# Sheet2.net
KiCad netlist of a schematic drawn in Altium Designer
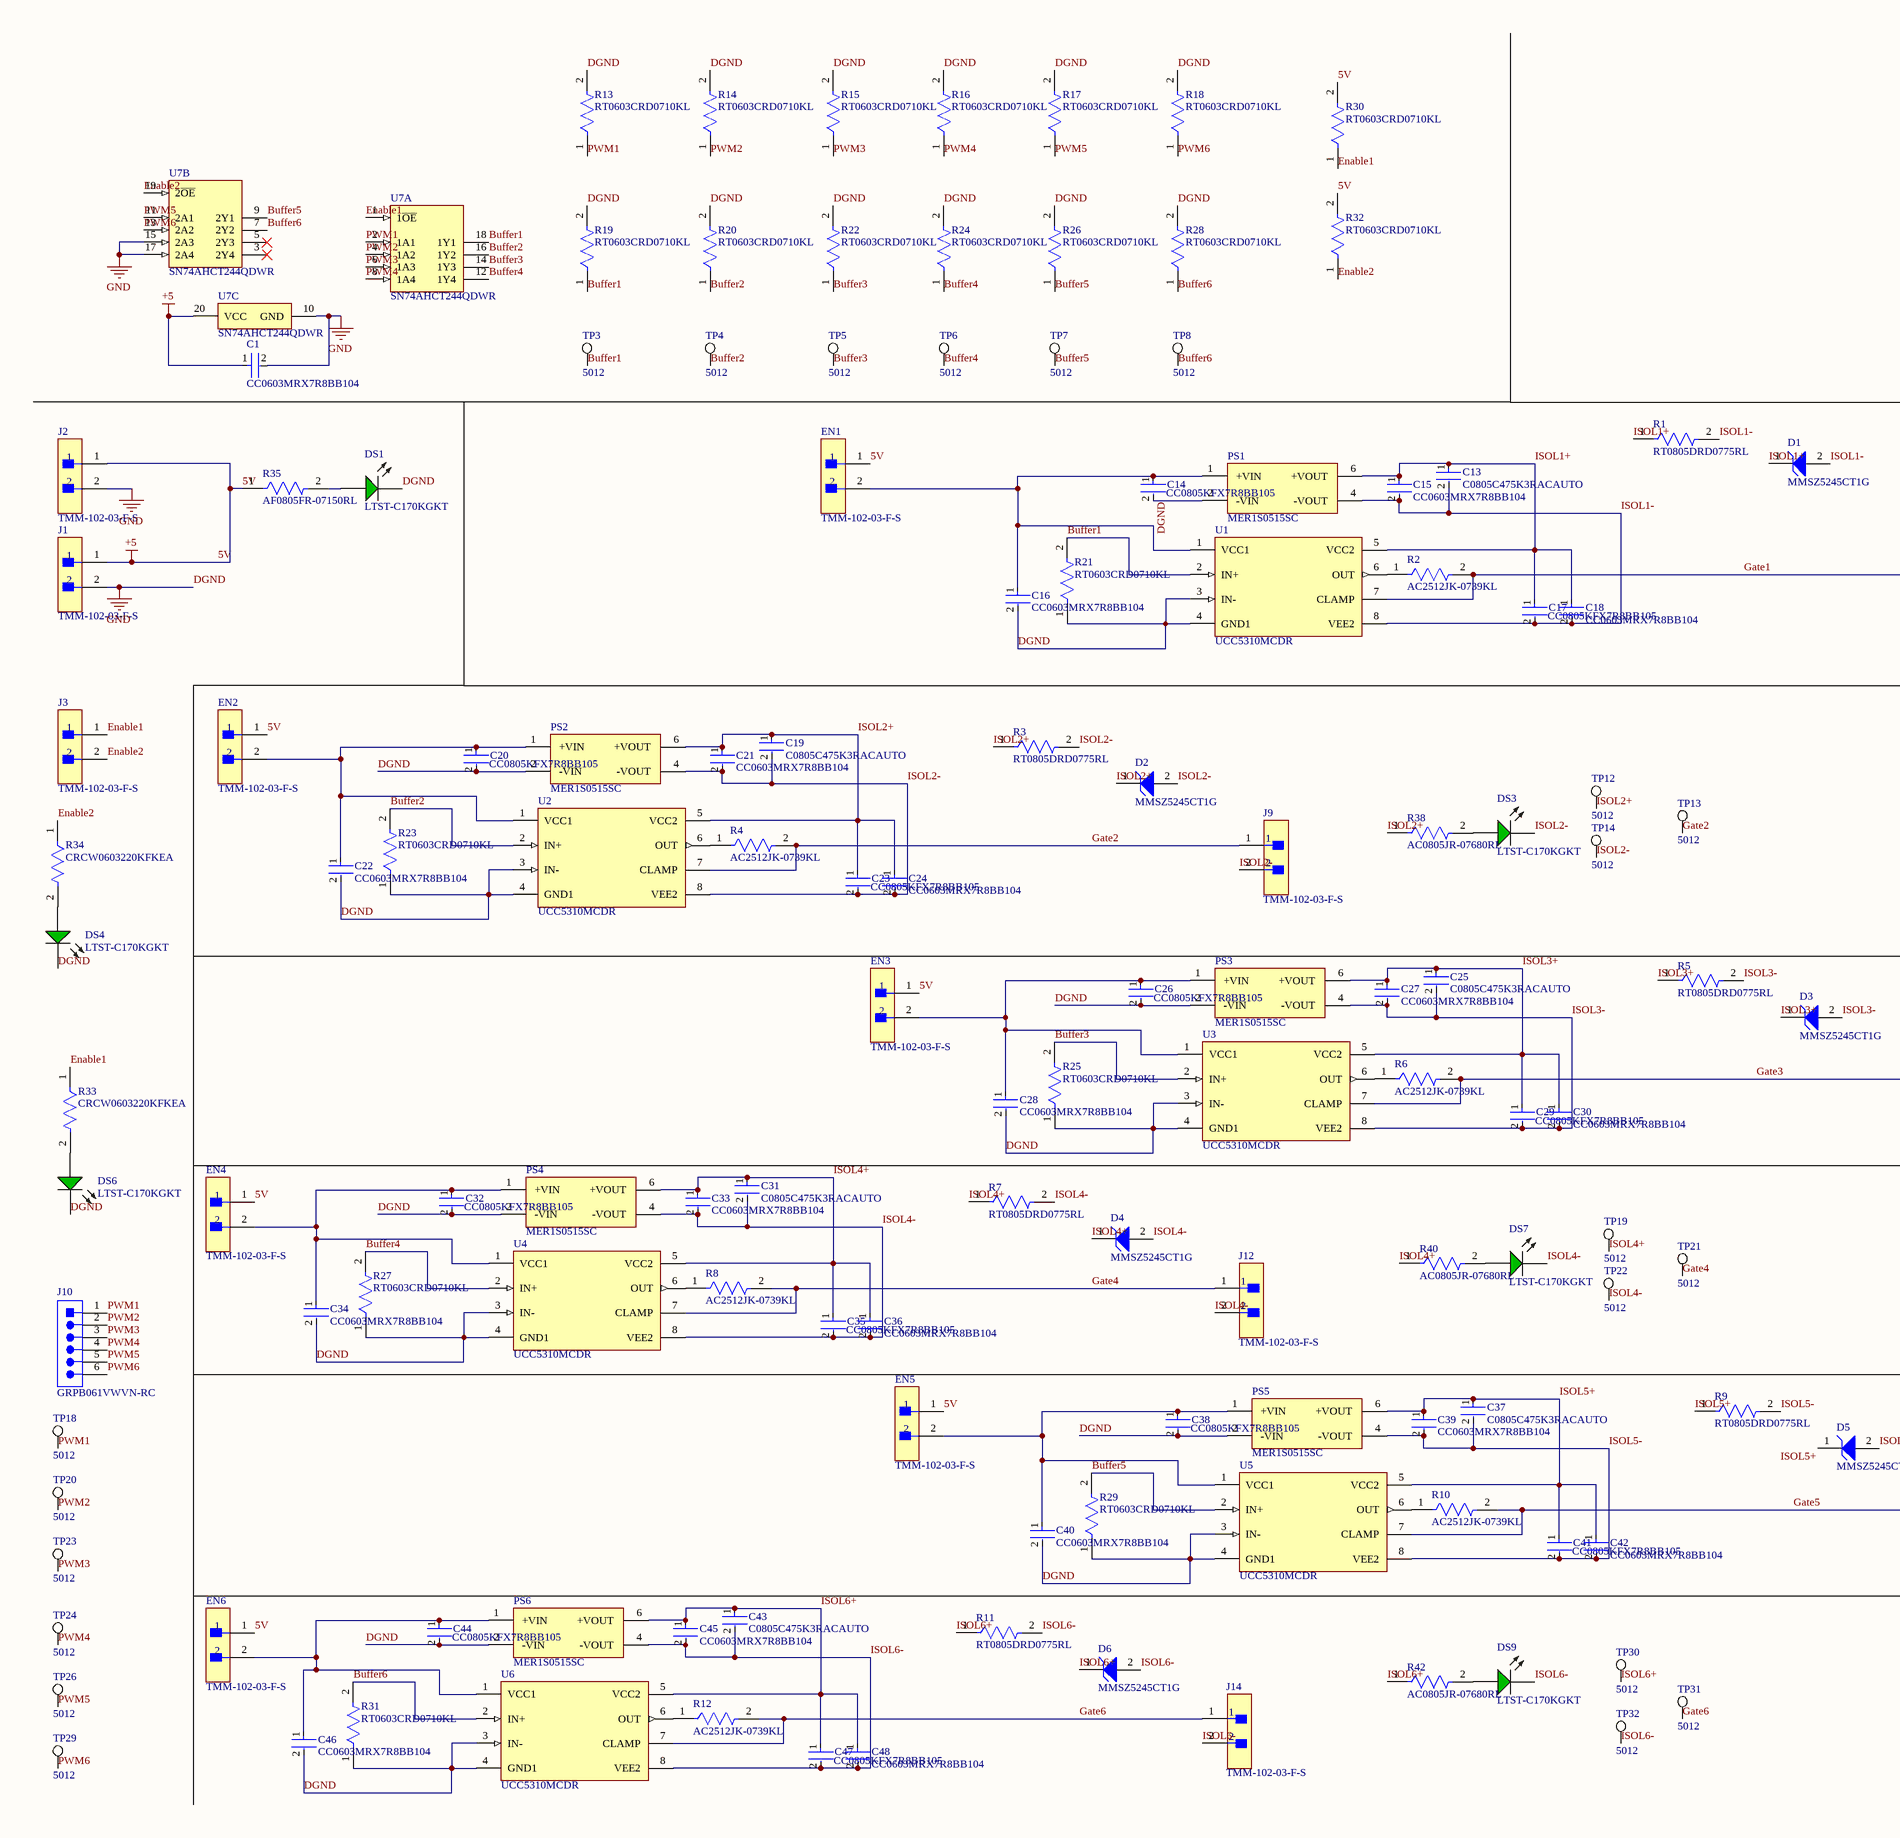
[diagram p0: Sheet2.SchDoc, left]
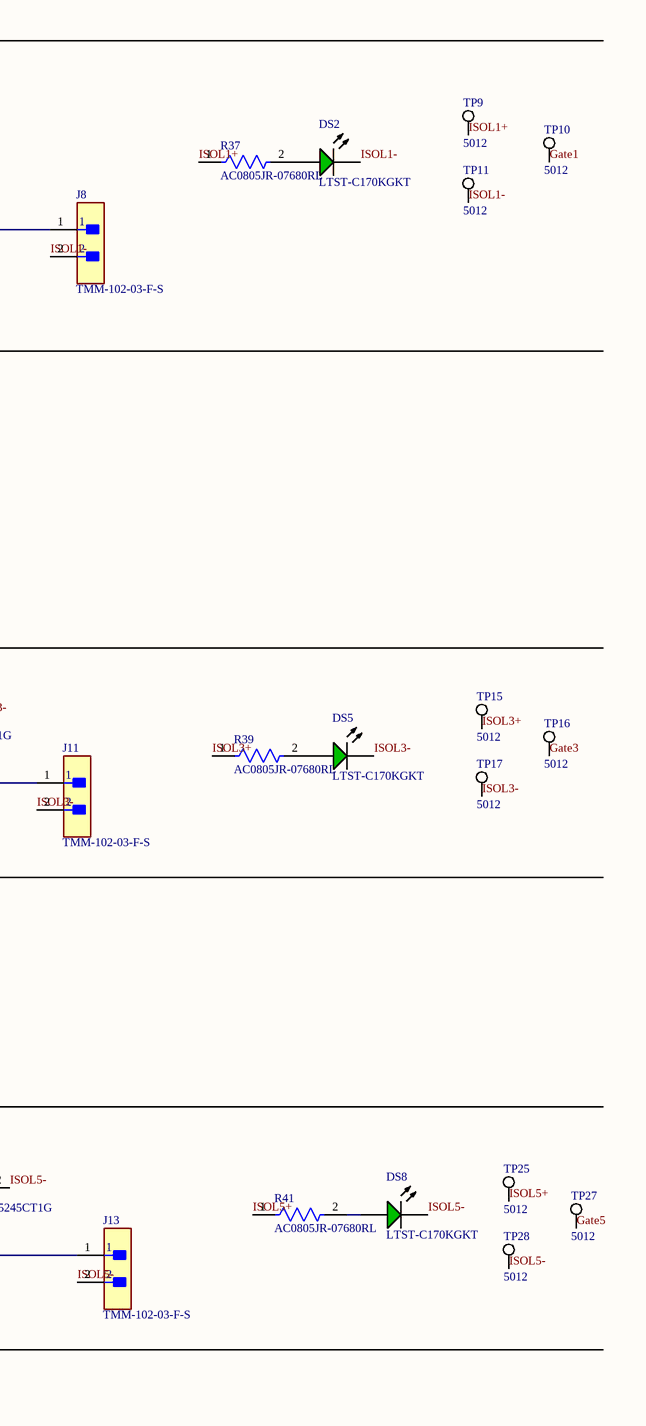
[diagram p1: Sheet2.SchDoc, right]

(export (version "E")
  (design (tool "Eeschema 10.0.6"))
  (components
    (comp (ref "C1")
      (value "CC0603MRX7R8BB104")
      (footprint "FP-CC0603-DA-MFG")
      (description "CAP CER 0.1UF 25V X7R 0603")
      (fields
        (field (name "TOLERANCE") "0.2")
        (field (name "OCTOPART") "https://octopart.com/cc0603mrx7r8bb104-yageo-12817663")
      )
      (libsource (lib "Altium Content Vault") (part "11868f565c42a9108669ba33697ecf6"))
    )
    (comp (ref "C13")
      (value "C0805C475K3RACAUTO")
      (footprint "FP-C0805C475K3RACAUTO-MFG")
      (description "CAP CER 0805 4.7UF 25V X7R  10%")
      (libsource (lib "Altium Content Vault") (part "b4654b650e69147ec39a6b967a45e02"))
    )
    (comp (ref "C14")
      (value "CC0805KFX7R8BB105")
      (footprint "FP-CC0805-0_85-MFG")
      (description "CC0805 1 uF X7R 10.00% 25 V")
      (fields (field (name "MANUFACTURER") "Yageo") (field (name "TOLERANCE") "0.1"))
      (libsource (lib "Altium Content Vault") (part "11868f565c42a9108669ba33697ecf6"))
    )
    (comp (ref "C15")
      (value "CC0603MRX7R8BB104")
      (footprint "FP-CC0603-DA-MFG")
      (description "CAP CER 0.1UF 25V X7R 0603")
      (fields
        (field (name "TOLERANCE") "0.2")
        (field (name "OCTOPART") "https://octopart.com/cc0603mrx7r8bb104-yageo-12817663")
      )
      (libsource (lib "Altium Content Vault") (part "11868f565c42a9108669ba33697ecf6"))
    )
    (comp (ref "C16")
      (value "CC0603MRX7R8BB104")
      (footprint "FP-CC0603-DA-MFG")
      (description "CAP CER 0.1UF 25V X7R 0603")
      (fields
        (field (name "TOLERANCE") "0.2")
        (field (name "OCTOPART") "https://octopart.com/cc0603mrx7r8bb104-yageo-12817663")
      )
      (libsource (lib "Altium Content Vault") (part "11868f565c42a9108669ba33697ecf6"))
    )
    (comp (ref "C17")
      (value "CC0805KFX7R8BB105")
      (footprint "FP-CC0805-0_85-MFG")
      (description "CC0805 1 uF X7R 10.00% 25 V")
      (fields (field (name "MANUFACTURER") "Yageo") (field (name "TOLERANCE") "0.1"))
      (libsource (lib "Altium Content Vault") (part "11868f565c42a9108669ba33697ecf6"))
    )
    (comp (ref "C18")
      (value "CC0603MRX7R8BB104")
      (footprint "FP-CC0603-DA-MFG")
      (description "CAP CER 0.1UF 25V X7R 0603")
      (fields
        (field (name "TOLERANCE") "0.2")
        (field (name "OCTOPART") "https://octopart.com/cc0603mrx7r8bb104-yageo-12817663")
      )
      (libsource (lib "Altium Content Vault") (part "11868f565c42a9108669ba33697ecf6"))
    )
    (comp (ref "C19")
      (value "C0805C475K3RACAUTO")
      (footprint "FP-C0805C475K3RACAUTO-MFG")
      (description "CAP CER 0805 4.7UF 25V X7R  10%")
      (libsource (lib "Altium Content Vault") (part "b4654b650e69147ec39a6b967a45e02"))
    )
    (comp (ref "C20")
      (value "CC0805KFX7R8BB105")
      (footprint "FP-CC0805-0_85-MFG")
      (description "CC0805 1 uF X7R 10.00% 25 V")
      (fields (field (name "MANUFACTURER") "Yageo") (field (name "TOLERANCE") "0.1"))
      (libsource (lib "Altium Content Vault") (part "11868f565c42a9108669ba33697ecf6"))
    )
    (comp (ref "C21")
      (value "CC0603MRX7R8BB104")
      (footprint "FP-CC0603-DA-MFG")
      (description "CAP CER 0.1UF 25V X7R 0603")
      (fields
        (field (name "TOLERANCE") "0.2")
        (field (name "OCTOPART") "https://octopart.com/cc0603mrx7r8bb104-yageo-12817663")
      )
      (libsource (lib "Altium Content Vault") (part "11868f565c42a9108669ba33697ecf6"))
    )
    (comp (ref "C22")
      (value "CC0603MRX7R8BB104")
      (footprint "FP-CC0603-DA-MFG")
      (description "CAP CER 0.1UF 25V X7R 0603")
      (fields
        (field (name "TOLERANCE") "0.2")
        (field (name "OCTOPART") "https://octopart.com/cc0603mrx7r8bb104-yageo-12817663")
      )
      (libsource (lib "Altium Content Vault") (part "11868f565c42a9108669ba33697ecf6"))
    )
    (comp (ref "C23")
      (value "CC0805KFX7R8BB105")
      (footprint "FP-CC0805-0_85-MFG")
      (description "CC0805 1 uF X7R 10.00% 25 V")
      (fields (field (name "MANUFACTURER") "Yageo") (field (name "TOLERANCE") "0.1"))
      (libsource (lib "Altium Content Vault") (part "11868f565c42a9108669ba33697ecf6"))
    )
    (comp (ref "C24")
      (value "CC0603MRX7R8BB104")
      (footprint "FP-CC0603-DA-MFG")
      (description "CAP CER 0.1UF 25V X7R 0603")
      (fields
        (field (name "TOLERANCE") "0.2")
        (field (name "OCTOPART") "https://octopart.com/cc0603mrx7r8bb104-yageo-12817663")
      )
      (libsource (lib "Altium Content Vault") (part "11868f565c42a9108669ba33697ecf6"))
    )
    (comp (ref "C25")
      (value "C0805C475K3RACAUTO")
      (footprint "FP-C0805C475K3RACAUTO-MFG")
      (description "CAP CER 0805 4.7UF 25V X7R  10%")
      (libsource (lib "Altium Content Vault") (part "b4654b650e69147ec39a6b967a45e02"))
    )
    (comp (ref "C26")
      (value "CC0805KFX7R8BB105")
      (footprint "FP-CC0805-0_85-MFG")
      (description "CC0805 1 uF X7R 10.00% 25 V")
      (fields (field (name "MANUFACTURER") "Yageo") (field (name "TOLERANCE") "0.1"))
      (libsource (lib "Altium Content Vault") (part "11868f565c42a9108669ba33697ecf6"))
    )
    (comp (ref "C27")
      (value "CC0603MRX7R8BB104")
      (footprint "FP-CC0603-DA-MFG")
      (description "CAP CER 0.1UF 25V X7R 0603")
      (fields
        (field (name "TOLERANCE") "0.2")
        (field (name "OCTOPART") "https://octopart.com/cc0603mrx7r8bb104-yageo-12817663")
      )
      (libsource (lib "Altium Content Vault") (part "11868f565c42a9108669ba33697ecf6"))
    )
    (comp (ref "C28")
      (value "CC0603MRX7R8BB104")
      (footprint "FP-CC0603-DA-MFG")
      (description "CAP CER 0.1UF 25V X7R 0603")
      (fields
        (field (name "TOLERANCE") "0.2")
        (field (name "OCTOPART") "https://octopart.com/cc0603mrx7r8bb104-yageo-12817663")
      )
      (libsource (lib "Altium Content Vault") (part "11868f565c42a9108669ba33697ecf6"))
    )
    (comp (ref "C29")
      (value "CC0805KFX7R8BB105")
      (footprint "FP-CC0805-0_85-MFG")
      (description "CC0805 1 uF X7R 10.00% 25 V")
      (fields (field (name "MANUFACTURER") "Yageo") (field (name "TOLERANCE") "0.1"))
      (libsource (lib "Altium Content Vault") (part "11868f565c42a9108669ba33697ecf6"))
    )
    (comp (ref "C30")
      (value "CC0603MRX7R8BB104")
      (footprint "FP-CC0603-DA-MFG")
      (description "CAP CER 0.1UF 25V X7R 0603")
      (fields
        (field (name "TOLERANCE") "0.2")
        (field (name "OCTOPART") "https://octopart.com/cc0603mrx7r8bb104-yageo-12817663")
      )
      (libsource (lib "Altium Content Vault") (part "11868f565c42a9108669ba33697ecf6"))
    )
    (comp (ref "C31")
      (value "C0805C475K3RACAUTO")
      (footprint "FP-C0805C475K3RACAUTO-MFG")
      (description "CAP CER 0805 4.7UF 25V X7R  10%")
      (libsource (lib "Altium Content Vault") (part "b4654b650e69147ec39a6b967a45e02"))
    )
    (comp (ref "C32")
      (value "CC0805KFX7R8BB105")
      (footprint "FP-CC0805-0_85-MFG")
      (description "CC0805 1 uF X7R 10.00% 25 V")
      (fields (field (name "MANUFACTURER") "Yageo") (field (name "TOLERANCE") "0.1"))
      (libsource (lib "Altium Content Vault") (part "11868f565c42a9108669ba33697ecf6"))
    )
    (comp (ref "C33")
      (value "CC0603MRX7R8BB104")
      (footprint "FP-CC0603-DA-MFG")
      (description "CAP CER 0.1UF 25V X7R 0603")
      (fields
        (field (name "TOLERANCE") "0.2")
        (field (name "OCTOPART") "https://octopart.com/cc0603mrx7r8bb104-yageo-12817663")
      )
      (libsource (lib "Altium Content Vault") (part "11868f565c42a9108669ba33697ecf6"))
    )
    (comp (ref "C34")
      (value "CC0603MRX7R8BB104")
      (footprint "FP-CC0603-DA-MFG")
      (description "CAP CER 0.1UF 25V X7R 0603")
      (fields
        (field (name "TOLERANCE") "0.2")
        (field (name "OCTOPART") "https://octopart.com/cc0603mrx7r8bb104-yageo-12817663")
      )
      (libsource (lib "Altium Content Vault") (part "11868f565c42a9108669ba33697ecf6"))
    )
    (comp (ref "C35")
      (value "CC0805KFX7R8BB105")
      (footprint "FP-CC0805-0_85-MFG")
      (description "CC0805 1 uF X7R 10.00% 25 V")
      (fields (field (name "MANUFACTURER") "Yageo") (field (name "TOLERANCE") "0.1"))
      (libsource (lib "Altium Content Vault") (part "11868f565c42a9108669ba33697ecf6"))
    )
    (comp (ref "C36")
      (value "CC0603MRX7R8BB104")
      (footprint "FP-CC0603-DA-MFG")
      (description "CAP CER 0.1UF 25V X7R 0603")
      (fields
        (field (name "TOLERANCE") "0.2")
        (field (name "OCTOPART") "https://octopart.com/cc0603mrx7r8bb104-yageo-12817663")
      )
      (libsource (lib "Altium Content Vault") (part "11868f565c42a9108669ba33697ecf6"))
    )
    (comp (ref "C37")
      (value "C0805C475K3RACAUTO")
      (footprint "FP-C0805C475K3RACAUTO-MFG")
      (description "CAP CER 0805 4.7UF 25V X7R  10%")
      (libsource (lib "Altium Content Vault") (part "b4654b650e69147ec39a6b967a45e02"))
    )
    (comp (ref "C38")
      (value "CC0805KFX7R8BB105")
      (footprint "FP-CC0805-0_85-MFG")
      (description "CC0805 1 uF X7R 10.00% 25 V")
      (fields (field (name "MANUFACTURER") "Yageo") (field (name "TOLERANCE") "0.1"))
      (libsource (lib "Altium Content Vault") (part "11868f565c42a9108669ba33697ecf6"))
    )
    (comp (ref "C39")
      (value "CC0603MRX7R8BB104")
      (footprint "FP-CC0603-DA-MFG")
      (description "CAP CER 0.1UF 25V X7R 0603")
      (fields
        (field (name "TOLERANCE") "0.2")
        (field (name "OCTOPART") "https://octopart.com/cc0603mrx7r8bb104-yageo-12817663")
      )
      (libsource (lib "Altium Content Vault") (part "11868f565c42a9108669ba33697ecf6"))
    )
    (comp (ref "C40")
      (value "CC0603MRX7R8BB104")
      (footprint "FP-CC0603-DA-MFG")
      (description "CAP CER 0.1UF 25V X7R 0603")
      (fields
        (field (name "TOLERANCE") "0.2")
        (field (name "OCTOPART") "https://octopart.com/cc0603mrx7r8bb104-yageo-12817663")
      )
      (libsource (lib "Altium Content Vault") (part "11868f565c42a9108669ba33697ecf6"))
    )
    (comp (ref "C41")
      (value "CC0805KFX7R8BB105")
      (footprint "FP-CC0805-0_85-MFG")
      (description "CC0805 1 uF X7R 10.00% 25 V")
      (fields (field (name "MANUFACTURER") "Yageo") (field (name "TOLERANCE") "0.1"))
      (libsource (lib "Altium Content Vault") (part "11868f565c42a9108669ba33697ecf6"))
    )
    (comp (ref "C42")
      (value "CC0603MRX7R8BB104")
      (footprint "FP-CC0603-DA-MFG")
      (description "CAP CER 0.1UF 25V X7R 0603")
      (fields
        (field (name "TOLERANCE") "0.2")
        (field (name "OCTOPART") "https://octopart.com/cc0603mrx7r8bb104-yageo-12817663")
      )
      (libsource (lib "Altium Content Vault") (part "11868f565c42a9108669ba33697ecf6"))
    )
    (comp (ref "C43")
      (value "C0805C475K3RACAUTO")
      (footprint "FP-C0805C475K3RACAUTO-MFG")
      (description "CAP CER 0805 4.7UF 25V X7R  10%")
      (libsource (lib "Altium Content Vault") (part "b4654b650e69147ec39a6b967a45e02"))
    )
    (comp (ref "C44")
      (value "CC0805KFX7R8BB105")
      (footprint "FP-CC0805-0_85-MFG")
      (description "CC0805 1 uF X7R 10.00% 25 V")
      (fields (field (name "MANUFACTURER") "Yageo") (field (name "TOLERANCE") "0.1"))
      (libsource (lib "Altium Content Vault") (part "11868f565c42a9108669ba33697ecf6"))
    )
    (comp (ref "C45")
      (value "CC0603MRX7R8BB104")
      (footprint "FP-CC0603-DA-MFG")
      (description "CAP CER 0.1UF 25V X7R 0603")
      (fields
        (field (name "TOLERANCE") "0.2")
        (field (name "OCTOPART") "https://octopart.com/cc0603mrx7r8bb104-yageo-12817663")
      )
      (libsource (lib "Altium Content Vault") (part "11868f565c42a9108669ba33697ecf6"))
    )
    (comp (ref "C46")
      (value "CC0603MRX7R8BB104")
      (footprint "FP-CC0603-DA-MFG")
      (description "CAP CER 0.1UF 25V X7R 0603")
      (fields
        (field (name "TOLERANCE") "0.2")
        (field (name "OCTOPART") "https://octopart.com/cc0603mrx7r8bb104-yageo-12817663")
      )
      (libsource (lib "Altium Content Vault") (part "11868f565c42a9108669ba33697ecf6"))
    )
    (comp (ref "C47")
      (value "CC0805KFX7R8BB105")
      (footprint "FP-CC0805-0_85-MFG")
      (description "CC0805 1 uF X7R 10.00% 25 V")
      (fields (field (name "MANUFACTURER") "Yageo") (field (name "TOLERANCE") "0.1"))
      (libsource (lib "Altium Content Vault") (part "11868f565c42a9108669ba33697ecf6"))
    )
    (comp (ref "C48")
      (value "CC0603MRX7R8BB104")
      (footprint "FP-CC0603-DA-MFG")
      (description "CAP CER 0.1UF 25V X7R 0603")
      (fields
        (field (name "TOLERANCE") "0.2")
        (field (name "OCTOPART") "https://octopart.com/cc0603mrx7r8bb104-yageo-12817663")
      )
      (libsource (lib "Altium Content Vault") (part "11868f565c42a9108669ba33697ecf6"))
    )
    (comp (ref "D1")
      (value "MMSZ5245CT1G")
      (footprint "ONSC-SOD-123-2-425-04_V")
      (description "Zener Voltage Regulator, 500 mW, 2-Pin SOD-123, Pb-Free, Tape and Reel")
      (fields (field (name "MANUFACTURER") "On Semiconductor"))
      (libsource (lib "Altium Content Vault") (part "ONSC-K1A2-2"))
    )
    (comp (ref "D2")
      (value "MMSZ5245CT1G")
      (footprint "ONSC-SOD-123-2-425-04_V")
      (description "Zener Voltage Regulator, 500 mW, 2-Pin SOD-123, Pb-Free, Tape and Reel")
      (fields (field (name "MANUFACTURER") "On Semiconductor"))
      (libsource (lib "Altium Content Vault") (part "ONSC-K1A2-2"))
    )
    (comp (ref "D3")
      (value "MMSZ5245CT1G")
      (footprint "ONSC-SOD-123-2-425-04_V")
      (description "Zener Voltage Regulator, 500 mW, 2-Pin SOD-123, Pb-Free, Tape and Reel")
      (fields (field (name "MANUFACTURER") "On Semiconductor"))
      (libsource (lib "Altium Content Vault") (part "ONSC-K1A2-2"))
    )
    (comp (ref "D4")
      (value "MMSZ5245CT1G")
      (footprint "ONSC-SOD-123-2-425-04_V")
      (description "Zener Voltage Regulator, 500 mW, 2-Pin SOD-123, Pb-Free, Tape and Reel")
      (fields (field (name "MANUFACTURER") "On Semiconductor"))
      (libsource (lib "Altium Content Vault") (part "ONSC-K1A2-2"))
    )
    (comp (ref "D5")
      (value "MMSZ5245CT1G")
      (footprint "ONSC-SOD-123-2-425-04_V")
      (description "Zener Voltage Regulator, 500 mW, 2-Pin SOD-123, Pb-Free, Tape and Reel")
      (fields (field (name "MANUFACTURER") "On Semiconductor"))
      (libsource (lib "Altium Content Vault") (part "ONSC-K1A2-2"))
    )
    (comp (ref "D6")
      (value "MMSZ5245CT1G")
      (footprint "ONSC-SOD-123-2-425-04_V")
      (description "Zener Voltage Regulator, 500 mW, 2-Pin SOD-123, Pb-Free, Tape and Reel")
      (fields (field (name "MANUFACTURER") "On Semiconductor"))
      (libsource (lib "Altium Content Vault") (part "ONSC-K1A2-2"))
    )
    (comp (ref "DS1")
      (value "LTST-C170KGKT")
      (footprint "LTST-LTST-C170KGKT-2_V")
      (description "Ultra Bright AlInGaP Chip LED, 75 mW, -55 to 85 degC, 2-Pin SMD (0805), RoHS, Tape and Reel")
      (fields (field (name "MANUFACTURER") "Lite-On"))
      (libsource (lib "Altium Content Vault") (part "LED-GREEN-KA-2"))
    )
    (comp (ref "DS2")
      (value "LTST-C170KGKT")
      (footprint "LTST-LTST-C170KGKT-2_V")
      (description "Ultra Bright AlInGaP Chip LED, 75 mW, -55 to 85 degC, 2-Pin SMD (0805), RoHS, Tape and Reel")
      (fields (field (name "MANUFACTURER") "Lite-On"))
      (libsource (lib "Altium Content Vault") (part "LED-GREEN-KA-2"))
    )
    (comp (ref "DS3")
      (value "LTST-C170KGKT")
      (footprint "LTST-LTST-C170KGKT-2_V")
      (description "Ultra Bright AlInGaP Chip LED, 75 mW, -55 to 85 degC, 2-Pin SMD (0805), RoHS, Tape and Reel")
      (fields (field (name "MANUFACTURER") "Lite-On"))
      (libsource (lib "Altium Content Vault") (part "LED-GREEN-KA-2"))
    )
    (comp (ref "DS4")
      (value "LTST-C170KGKT")
      (footprint "LTST-LTST-C170KGKT-2_V")
      (description "Ultra Bright AlInGaP Chip LED, 75 mW, -55 to 85 degC, 2-Pin SMD (0805), RoHS, Tape and Reel")
      (fields (field (name "MANUFACTURER") "Lite-On"))
      (libsource (lib "Altium Content Vault") (part "LED-GREEN-KA-2"))
    )
    (comp (ref "DS5")
      (value "LTST-C170KGKT")
      (footprint "LTST-LTST-C170KGKT-2_V")
      (description "Ultra Bright AlInGaP Chip LED, 75 mW, -55 to 85 degC, 2-Pin SMD (0805), RoHS, Tape and Reel")
      (fields (field (name "MANUFACTURER") "Lite-On"))
      (libsource (lib "Altium Content Vault") (part "LED-GREEN-KA-2"))
    )
    (comp (ref "DS6")
      (value "LTST-C170KGKT")
      (footprint "LTST-LTST-C170KGKT-2_V")
      (description "Ultra Bright AlInGaP Chip LED, 75 mW, -55 to 85 degC, 2-Pin SMD (0805), RoHS, Tape and Reel")
      (fields (field (name "MANUFACTURER") "Lite-On"))
      (libsource (lib "Altium Content Vault") (part "LED-GREEN-KA-2"))
    )
    (comp (ref "DS7")
      (value "LTST-C170KGKT")
      (footprint "LTST-LTST-C170KGKT-2_V")
      (description "Ultra Bright AlInGaP Chip LED, 75 mW, -55 to 85 degC, 2-Pin SMD (0805), RoHS, Tape and Reel")
      (fields (field (name "MANUFACTURER") "Lite-On"))
      (libsource (lib "Altium Content Vault") (part "LED-GREEN-KA-2"))
    )
    (comp (ref "DS8")
      (value "LTST-C170KGKT")
      (footprint "LTST-LTST-C170KGKT-2_V")
      (description "Ultra Bright AlInGaP Chip LED, 75 mW, -55 to 85 degC, 2-Pin SMD (0805), RoHS, Tape and Reel")
      (fields (field (name "MANUFACTURER") "Lite-On"))
      (libsource (lib "Altium Content Vault") (part "LED-GREEN-KA-2"))
    )
    (comp (ref "DS9")
      (value "LTST-C170KGKT")
      (footprint "LTST-LTST-C170KGKT-2_V")
      (description "Ultra Bright AlInGaP Chip LED, 75 mW, -55 to 85 degC, 2-Pin SMD (0805), RoHS, Tape and Reel")
      (fields (field (name "MANUFACTURER") "Lite-On"))
      (libsource (lib "Altium Content Vault") (part "LED-GREEN-KA-2"))
    )
    (comp (ref "EN1")
      (value "TMM-102-03-F-S")
      (footprint "GPIO_Headers:PinHeader_1x02_P2.54mm_Vertical")
      (description "CONN HEADER VERT 2POS 2MM")
      (libsource (lib "Altium Content Vault") (part "3bc925449376181038e59eaffc5286c"))
    )
    (comp (ref "EN2")
      (value "TMM-102-03-F-S")
      (footprint "GPIO_Headers:PinHeader_1x02_P2.54mm_Vertical")
      (description "CONN HEADER VERT 2POS 2MM")
      (libsource (lib "Altium Content Vault") (part "3bc925449376181038e59eaffc5286c"))
    )
    (comp (ref "EN3")
      (value "TMM-102-03-F-S")
      (footprint "GPIO_Headers:PinHeader_1x02_P2.54mm_Vertical")
      (description "CONN HEADER VERT 2POS 2MM")
      (libsource (lib "Altium Content Vault") (part "3bc925449376181038e59eaffc5286c"))
    )
    (comp (ref "EN4")
      (value "TMM-102-03-F-S")
      (footprint "GPIO_Headers:PinHeader_1x02_P2.54mm_Vertical")
      (description "CONN HEADER VERT 2POS 2MM")
      (libsource (lib "Altium Content Vault") (part "3bc925449376181038e59eaffc5286c"))
    )
    (comp (ref "EN5")
      (value "TMM-102-03-F-S")
      (footprint "GPIO_Headers:PinHeader_1x02_P2.54mm_Vertical")
      (description "CONN HEADER VERT 2POS 2MM")
      (libsource (lib "Altium Content Vault") (part "3bc925449376181038e59eaffc5286c"))
    )
    (comp (ref "EN6")
      (value "TMM-102-03-F-S")
      (footprint "GPIO_Headers:PinHeader_1x02_P2.54mm_Vertical")
      (description "CONN HEADER VERT 2POS 2MM")
      (libsource (lib "Altium Content Vault") (part "3bc925449376181038e59eaffc5286c"))
    )
    (comp (ref "J1")
      (value "TMM-102-03-F-S")
      (footprint "GPIO_Headers:PinHeader_1x02_P2.54mm_Vertical")
      (description "CONN HEADER VERT 2POS 2MM")
      (libsource (lib "Altium Content Vault") (part "3bc925449376181038e59eaffc5286c"))
    )
    (comp (ref "J2")
      (value "TMM-102-03-F-S")
      (footprint "GPIO_Headers:PinHeader_1x02_P2.54mm_Vertical")
      (description "CONN HEADER VERT 2POS 2MM")
      (libsource (lib "Altium Content Vault") (part "3bc925449376181038e59eaffc5286c"))
    )
    (comp (ref "J3")
      (value "TMM-102-03-F-S")
      (footprint "GPIO_Headers:PinHeader_1x02_P2.54mm_Vertical")
      (description "CONN HEADER VERT 2POS 2MM")
      (libsource (lib "Altium Content Vault") (part "3bc925449376181038e59eaffc5286c"))
    )
    (comp (ref "J8")
      (value "TMM-102-03-F-S")
      (footprint "GPIO_Headers:PinHeader_1x02_P2.54mm_Vertical")
      (description "CONN HEADER VERT 2POS 2MM")
      (libsource (lib "") (part "3bc925449376181038e59eaffc5286c_1"))
    )
    (comp (ref "J9")
      (value "TMM-102-03-F-S")
      (footprint "GPIO_Headers:PinHeader_1x02_P2.54mm_Vertical")
      (description "CONN HEADER VERT 2POS 2MM")
      (libsource (lib "") (part "3bc925449376181038e59eaffc5286c_1"))
    )
    (comp (ref "J10")
      (value "GRPB061VWVN-RC")
      (footprint "GPIO_Headers:PinHeader_1x06_P2.54mm_Vertical")
      (fields (field (name "MANUFACTURER") "Sullins"))
      (libsource (lib "Altium Content Vault") (part "CN-1P-M-R6"))
    )
    (comp (ref "J11")
      (value "TMM-102-03-F-S")
      (footprint "GPIO_Headers:PinHeader_1x02_P2.54mm_Vertical")
      (description "CONN HEADER VERT 2POS 2MM")
      (libsource (lib "") (part "3bc925449376181038e59eaffc5286c_1"))
    )
    (comp (ref "J12")
      (value "TMM-102-03-F-S")
      (footprint "GPIO_Headers:PinHeader_1x02_P2.54mm_Vertical")
      (description "CONN HEADER VERT 2POS 2MM")
      (libsource (lib "") (part "3bc925449376181038e59eaffc5286c_1"))
    )
    (comp (ref "J13")
      (value "TMM-102-03-F-S")
      (footprint "GPIO_Headers:PinHeader_1x02_P2.54mm_Vertical")
      (description "CONN HEADER VERT 2POS 2MM")
      (libsource (lib "") (part "3bc925449376181038e59eaffc5286c_1"))
    )
    (comp (ref "J14")
      (value "TMM-102-03-F-S")
      (footprint "GPIO_Headers:PinHeader_1x02_P2.54mm_Vertical")
      (description "CONN HEADER VERT 2POS 2MM")
      (libsource (lib "") (part "3bc925449376181038e59eaffc5286c_1"))
    )
    (comp (ref "PS1")
      (value "MER1S0515SC")
      (footprint "MER1S0515SC_MFG")
      (description "Module DC-DC 5VIN 1-OUT 15V 0.067A 1W 4-Pin SIP Tube")
      (libsource (lib "Altium Content Vault") (part "aca5a9e5ed4e940d1217dfa819842fb"))
    )
    (comp (ref "PS2")
      (value "MER1S0515SC")
      (footprint "MER1S0515SC_MFG")
      (description "Module DC-DC 5VIN 1-OUT 15V 0.067A 1W 4-Pin SIP Tube")
      (libsource (lib "Altium Content Vault") (part "aca5a9e5ed4e940d1217dfa819842fb"))
    )
    (comp (ref "PS3")
      (value "MER1S0515SC")
      (footprint "MER1S0515SC_MFG")
      (description "Module DC-DC 5VIN 1-OUT 15V 0.067A 1W 4-Pin SIP Tube")
      (libsource (lib "Altium Content Vault") (part "aca5a9e5ed4e940d1217dfa819842fb"))
    )
    (comp (ref "PS4")
      (value "MER1S0515SC")
      (footprint "MER1S0515SC_MFG")
      (description "Module DC-DC 5VIN 1-OUT 15V 0.067A 1W 4-Pin SIP Tube")
      (libsource (lib "Altium Content Vault") (part "aca5a9e5ed4e940d1217dfa819842fb"))
    )
    (comp (ref "PS5")
      (value "MER1S0515SC")
      (footprint "MER1S0515SC_MFG")
      (description "Module DC-DC 5VIN 1-OUT 15V 0.067A 1W 4-Pin SIP Tube")
      (libsource (lib "Altium Content Vault") (part "aca5a9e5ed4e940d1217dfa819842fb"))
    )
    (comp (ref "PS6")
      (value "MER1S0515SC")
      (footprint "MER1S0515SC_MFG")
      (description "Module DC-DC 5VIN 1-OUT 15V 0.067A 1W 4-Pin SIP Tube")
      (libsource (lib "Altium Content Vault") (part "aca5a9e5ed4e940d1217dfa819842fb"))
    )
    (comp (ref "R1")
      (value "RT0805DRD0775RL")
      (footprint "FP-RT0805-MFG")
      (description "RES SMD 75 OHM 0.5% 1/8W 0805")
      (fields (field (name "TOLERANCE") "0.01") (field (name "MANUFACTURER") "Yageo"))
      (libsource (lib "Altium Content Vault") (part "1029c3af85768c4190bb7ad29bc67b5"))
    )
    (comp (ref "R2")
      (value "AC2512JK-0739KL")
      (footprint "FP-AC2512-MFG")
      (description "RES SMD 39K OHM 5% 1W 2512")
      (fields
        (field (name "OCTOPART") "https://octopart.com/ac2512jk-0739kl-yageo-71370377")
        (field (name "TOLERANCE") "0.05")
      )
      (libsource (lib "Altium Content Vault") (part "1029c3af85768c4190bb7ad29bc67b5"))
    )
    (comp (ref "R3")
      (value "RT0805DRD0775RL")
      (footprint "FP-RT0805-MFG")
      (description "RES SMD 75 OHM 0.5% 1/8W 0805")
      (fields (field (name "TOLERANCE") "0.01") (field (name "MANUFACTURER") "Yageo"))
      (libsource (lib "Altium Content Vault") (part "1029c3af85768c4190bb7ad29bc67b5"))
    )
    (comp (ref "R4")
      (value "AC2512JK-0739KL")
      (footprint "FP-AC2512-MFG")
      (description "RES SMD 39K OHM 5% 1W 2512")
      (fields
        (field (name "OCTOPART") "https://octopart.com/ac2512jk-0739kl-yageo-71370377")
        (field (name "TOLERANCE") "0.05")
      )
      (libsource (lib "Altium Content Vault") (part "1029c3af85768c4190bb7ad29bc67b5"))
    )
    (comp (ref "R5")
      (value "RT0805DRD0775RL")
      (footprint "FP-RT0805-MFG")
      (description "RES SMD 75 OHM 0.5% 1/8W 0805")
      (fields (field (name "TOLERANCE") "0.01") (field (name "MANUFACTURER") "Yageo"))
      (libsource (lib "Altium Content Vault") (part "1029c3af85768c4190bb7ad29bc67b5"))
    )
    (comp (ref "R6")
      (value "AC2512JK-0739KL")
      (footprint "FP-AC2512-MFG")
      (description "RES SMD 39K OHM 5% 1W 2512")
      (fields
        (field (name "OCTOPART") "https://octopart.com/ac2512jk-0739kl-yageo-71370377")
        (field (name "TOLERANCE") "0.05")
      )
      (libsource (lib "Altium Content Vault") (part "1029c3af85768c4190bb7ad29bc67b5"))
    )
    (comp (ref "R7")
      (value "RT0805DRD0775RL")
      (footprint "FP-RT0805-MFG")
      (description "RES SMD 75 OHM 0.5% 1/8W 0805")
      (fields (field (name "TOLERANCE") "0.01") (field (name "MANUFACTURER") "Yageo"))
      (libsource (lib "Altium Content Vault") (part "1029c3af85768c4190bb7ad29bc67b5"))
    )
    (comp (ref "R8")
      (value "AC2512JK-0739KL")
      (footprint "FP-AC2512-MFG")
      (description "RES SMD 39K OHM 5% 1W 2512")
      (fields
        (field (name "OCTOPART") "https://octopart.com/ac2512jk-0739kl-yageo-71370377")
        (field (name "TOLERANCE") "0.05")
      )
      (libsource (lib "Altium Content Vault") (part "1029c3af85768c4190bb7ad29bc67b5"))
    )
    (comp (ref "R9")
      (value "RT0805DRD0775RL")
      (footprint "FP-RT0805-MFG")
      (description "RES SMD 75 OHM 0.5% 1/8W 0805")
      (fields (field (name "TOLERANCE") "0.01") (field (name "MANUFACTURER") "Yageo"))
      (libsource (lib "Altium Content Vault") (part "1029c3af85768c4190bb7ad29bc67b5"))
    )
    (comp (ref "R10")
      (value "AC2512JK-0739KL")
      (footprint "FP-AC2512-MFG")
      (description "RES SMD 39K OHM 5% 1W 2512")
      (fields
        (field (name "OCTOPART") "https://octopart.com/ac2512jk-0739kl-yageo-71370377")
        (field (name "TOLERANCE") "0.05")
      )
      (libsource (lib "Altium Content Vault") (part "1029c3af85768c4190bb7ad29bc67b5"))
    )
    (comp (ref "R11")
      (value "RT0805DRD0775RL")
      (footprint "FP-RT0805-MFG")
      (description "RES SMD 75 OHM 0.5% 1/8W 0805")
      (fields (field (name "TOLERANCE") "0.01") (field (name "MANUFACTURER") "Yageo"))
      (libsource (lib "Altium Content Vault") (part "1029c3af85768c4190bb7ad29bc67b5"))
    )
    (comp (ref "R12")
      (value "AC2512JK-0739KL")
      (footprint "FP-AC2512-MFG")
      (description "RES SMD 39K OHM 5% 1W 2512")
      (fields
        (field (name "OCTOPART") "https://octopart.com/ac2512jk-0739kl-yageo-71370377")
        (field (name "TOLERANCE") "0.05")
      )
      (libsource (lib "Altium Content Vault") (part "1029c3af85768c4190bb7ad29bc67b5"))
    )
    (comp (ref "R13")
      (value "RT0603CRD0710KL")
      (footprint "FP-RT0603-MFG")
      (description "RES SMD 10K OHM 0.25% 1/10W 0603")
      (fields (field (name "TOLERANCE") "0.0025") (field (name "MANUFACTURER") "Yageo"))
      (libsource (lib "Altium Content Vault") (part "1029c3af85768c4190bb7ad29bc67b5"))
    )
    (comp (ref "R14")
      (value "RT0603CRD0710KL")
      (footprint "FP-RT0603-MFG")
      (description "RES SMD 10K OHM 0.25% 1/10W 0603")
      (fields (field (name "TOLERANCE") "0.0025") (field (name "MANUFACTURER") "Yageo"))
      (libsource (lib "Altium Content Vault") (part "1029c3af85768c4190bb7ad29bc67b5"))
    )
    (comp (ref "R15")
      (value "RT0603CRD0710KL")
      (footprint "FP-RT0603-MFG")
      (description "RES SMD 10K OHM 0.25% 1/10W 0603")
      (fields (field (name "TOLERANCE") "0.0025") (field (name "MANUFACTURER") "Yageo"))
      (libsource (lib "Altium Content Vault") (part "1029c3af85768c4190bb7ad29bc67b5"))
    )
    (comp (ref "R16")
      (value "RT0603CRD0710KL")
      (footprint "FP-RT0603-MFG")
      (description "RES SMD 10K OHM 0.25% 1/10W 0603")
      (fields (field (name "TOLERANCE") "0.0025") (field (name "MANUFACTURER") "Yageo"))
      (libsource (lib "Altium Content Vault") (part "1029c3af85768c4190bb7ad29bc67b5"))
    )
    (comp (ref "R17")
      (value "RT0603CRD0710KL")
      (footprint "FP-RT0603-MFG")
      (description "RES SMD 10K OHM 0.25% 1/10W 0603")
      (fields (field (name "TOLERANCE") "0.0025") (field (name "MANUFACTURER") "Yageo"))
      (libsource (lib "Altium Content Vault") (part "1029c3af85768c4190bb7ad29bc67b5"))
    )
    (comp (ref "R18")
      (value "RT0603CRD0710KL")
      (footprint "FP-RT0603-MFG")
      (description "RES SMD 10K OHM 0.25% 1/10W 0603")
      (fields (field (name "TOLERANCE") "0.0025") (field (name "MANUFACTURER") "Yageo"))
      (libsource (lib "Altium Content Vault") (part "1029c3af85768c4190bb7ad29bc67b5"))
    )
    (comp (ref "R19")
      (value "RT0603CRD0710KL")
      (footprint "FP-RT0603-MFG")
      (description "RES SMD 10K OHM 0.25% 1/10W 0603")
      (fields (field (name "TOLERANCE") "0.0025") (field (name "MANUFACTURER") "Yageo"))
      (libsource (lib "Altium Content Vault") (part "1029c3af85768c4190bb7ad29bc67b5"))
    )
    (comp (ref "R20")
      (value "RT0603CRD0710KL")
      (footprint "FP-RT0603-MFG")
      (description "RES SMD 10K OHM 0.25% 1/10W 0603")
      (fields (field (name "TOLERANCE") "0.0025") (field (name "MANUFACTURER") "Yageo"))
      (libsource (lib "Altium Content Vault") (part "1029c3af85768c4190bb7ad29bc67b5"))
    )
    (comp (ref "R21")
      (value "RT0603CRD0710KL")
      (footprint "FP-RT0603-MFG")
      (description "RES SMD 10K OHM 0.25% 1/10W 0603")
      (fields (field (name "TOLERANCE") "0.0025") (field (name "MANUFACTURER") "Yageo"))
      (libsource (lib "Altium Content Vault") (part "1029c3af85768c4190bb7ad29bc67b5"))
    )
    (comp (ref "R22")
      (value "RT0603CRD0710KL")
      (footprint "FP-RT0603-MFG")
      (description "RES SMD 10K OHM 0.25% 1/10W 0603")
      (fields (field (name "TOLERANCE") "0.0025") (field (name "MANUFACTURER") "Yageo"))
      (libsource (lib "Altium Content Vault") (part "1029c3af85768c4190bb7ad29bc67b5"))
    )
    (comp (ref "R23")
      (value "RT0603CRD0710KL")
      (footprint "FP-RT0603-MFG")
      (description "RES SMD 10K OHM 0.25% 1/10W 0603")
      (fields (field (name "TOLERANCE") "0.0025") (field (name "MANUFACTURER") "Yageo"))
      (libsource (lib "Altium Content Vault") (part "1029c3af85768c4190bb7ad29bc67b5"))
    )
    (comp (ref "R24")
      (value "RT0603CRD0710KL")
      (footprint "FP-RT0603-MFG")
      (description "RES SMD 10K OHM 0.25% 1/10W 0603")
      (fields (field (name "TOLERANCE") "0.0025") (field (name "MANUFACTURER") "Yageo"))
      (libsource (lib "Altium Content Vault") (part "1029c3af85768c4190bb7ad29bc67b5"))
    )
    (comp (ref "R25")
      (value "RT0603CRD0710KL")
      (footprint "FP-RT0603-MFG")
      (description "RES SMD 10K OHM 0.25% 1/10W 0603")
      (fields (field (name "TOLERANCE") "0.0025") (field (name "MANUFACTURER") "Yageo"))
      (libsource (lib "Altium Content Vault") (part "1029c3af85768c4190bb7ad29bc67b5"))
    )
    (comp (ref "R26")
      (value "RT0603CRD0710KL")
      (footprint "FP-RT0603-MFG")
      (description "RES SMD 10K OHM 0.25% 1/10W 0603")
      (fields (field (name "TOLERANCE") "0.0025") (field (name "MANUFACTURER") "Yageo"))
      (libsource (lib "Altium Content Vault") (part "1029c3af85768c4190bb7ad29bc67b5"))
    )
    (comp (ref "R27")
      (value "RT0603CRD0710KL")
      (footprint "FP-RT0603-MFG")
      (description "RES SMD 10K OHM 0.25% 1/10W 0603")
      (fields (field (name "TOLERANCE") "0.0025") (field (name "MANUFACTURER") "Yageo"))
      (libsource (lib "Altium Content Vault") (part "1029c3af85768c4190bb7ad29bc67b5"))
    )
    (comp (ref "R28")
      (value "RT0603CRD0710KL")
      (footprint "FP-RT0603-MFG")
      (description "RES SMD 10K OHM 0.25% 1/10W 0603")
      (fields (field (name "TOLERANCE") "0.0025") (field (name "MANUFACTURER") "Yageo"))
      (libsource (lib "Altium Content Vault") (part "1029c3af85768c4190bb7ad29bc67b5"))
    )
    (comp (ref "R29")
      (value "RT0603CRD0710KL")
      (footprint "FP-RT0603-MFG")
      (description "RES SMD 10K OHM 0.25% 1/10W 0603")
      (fields (field (name "TOLERANCE") "0.0025") (field (name "MANUFACTURER") "Yageo"))
      (libsource (lib "Altium Content Vault") (part "1029c3af85768c4190bb7ad29bc67b5"))
    )
    (comp (ref "R30")
      (value "RT0603CRD0710KL")
      (footprint "FP-RT0603-MFG")
      (description "RES SMD 10K OHM 0.25% 1/10W 0603")
      (fields (field (name "TOLERANCE") "0.0025") (field (name "MANUFACTURER") "Yageo"))
      (libsource (lib "Altium Content Vault") (part "1029c3af85768c4190bb7ad29bc67b5"))
    )
    (comp (ref "R31")
      (value "RT0603CRD0710KL")
      (footprint "FP-RT0603-MFG")
      (description "RES SMD 10K OHM 0.25% 1/10W 0603")
      (fields (field (name "TOLERANCE") "0.0025") (field (name "MANUFACTURER") "Yageo"))
      (libsource (lib "Altium Content Vault") (part "1029c3af85768c4190bb7ad29bc67b5"))
    )
    (comp (ref "R32")
      (value "RT0603CRD0710KL")
      (footprint "FP-RT0603-MFG")
      (description "RES SMD 10K OHM 0.25% 1/10W 0603")
      (fields (field (name "TOLERANCE") "0.0025") (field (name "MANUFACTURER") "Yageo"))
      (libsource (lib "Altium Content Vault") (part "1029c3af85768c4190bb7ad29bc67b5"))
    )
    (comp (ref "R33")
      (value "CRCW0603220KFKEA")
      (footprint "FP-CRCW0603-e3-IPC_B")
      (description "RES Thick Film, 220kΩ, 1%, 0.1W, 100ppm/°C, 0603")
      (fields (field (name "TOLERANCE") "1%"))
      (libsource (lib "Altium Content Vault") (part "1029c3af85768c4190bb7ad29bc67b5"))
    )
    (comp (ref "R34")
      (value "CRCW0603220KFKEA")
      (footprint "FP-CRCW0603-e3-IPC_B")
      (description "RES Thick Film, 220kΩ, 1%, 0.1W, 100ppm/°C, 0603")
      (fields (field (name "TOLERANCE") "1%"))
      (libsource (lib "Altium Content Vault") (part "1029c3af85768c4190bb7ad29bc67b5"))
    )
    (comp (ref "R35")
      (value "AF0805FR-07150RL")
      (footprint "FP-AF0805-MFG")
      (description "Anti-Sulfurated Chip Resistor Automotive Grade 150Ω 1% 0.125W ±100ppm/°C 0805")
      (fields (field (name "TOLERANCE") "1%"))
      (libsource (lib "Altium Content Vault") (part "1029c3af85768c4190bb7ad29bc67b5"))
    )
    (comp (ref "R37")
      (value "AC0805JR-07680RL")
      (footprint "FP-AC0805-MFG")
      (description "RES SMD 680 OHM 5% 1/8W 0805")
      (fields (field (name "MANUFACTURER") "Yageo") (field (name "TOLERANCE") "0.05"))
      (libsource (lib "Altium Content Vault") (part "1029c3af85768c4190bb7ad29bc67b5"))
    )
    (comp (ref "R38")
      (value "AC0805JR-07680RL")
      (footprint "FP-AC0805-MFG")
      (description "RES SMD 680 OHM 5% 1/8W 0805")
      (fields (field (name "MANUFACTURER") "Yageo") (field (name "TOLERANCE") "0.05"))
      (libsource (lib "Altium Content Vault") (part "1029c3af85768c4190bb7ad29bc67b5"))
    )
    (comp (ref "R39")
      (value "AC0805JR-07680RL")
      (footprint "FP-AC0805-MFG")
      (description "RES SMD 680 OHM 5% 1/8W 0805")
      (fields (field (name "MANUFACTURER") "Yageo") (field (name "TOLERANCE") "0.05"))
      (libsource (lib "Altium Content Vault") (part "1029c3af85768c4190bb7ad29bc67b5"))
    )
    (comp (ref "R40")
      (value "AC0805JR-07680RL")
      (footprint "FP-AC0805-MFG")
      (description "RES SMD 680 OHM 5% 1/8W 0805")
      (fields (field (name "MANUFACTURER") "Yageo") (field (name "TOLERANCE") "0.05"))
      (libsource (lib "Altium Content Vault") (part "1029c3af85768c4190bb7ad29bc67b5"))
    )
    (comp (ref "R41")
      (value "AC0805JR-07680RL")
      (footprint "FP-AC0805-MFG")
      (description "RES SMD 680 OHM 5% 1/8W 0805")
      (fields (field (name "MANUFACTURER") "Yageo") (field (name "TOLERANCE") "0.05"))
      (libsource (lib "Altium Content Vault") (part "1029c3af85768c4190bb7ad29bc67b5"))
    )
    (comp (ref "R42")
      (value "AC0805JR-07680RL")
      (footprint "FP-AC0805-MFG")
      (description "RES SMD 680 OHM 5% 1/8W 0805")
      (fields (field (name "MANUFACTURER") "Yageo") (field (name "TOLERANCE") "0.05"))
      (libsource (lib "Altium Content Vault") (part "1029c3af85768c4190bb7ad29bc67b5"))
    )
    (comp (ref "TP3")
      (value "5012")
      (footprint "KSTN-5012_V")
      (description "Test Point, White, Through Hole, RoHS, Bulk")
      (fields (field (name "MANUFACTURER") "Keystone"))
      (libsource (lib "Altium Content Vault") (part "TESTPOINT_WHITE"))
    )
    (comp (ref "TP4")
      (value "5012")
      (footprint "KSTN-5012_V")
      (description "Test Point, White, Through Hole, RoHS, Bulk")
      (fields (field (name "MANUFACTURER") "Keystone"))
      (libsource (lib "Altium Content Vault") (part "TESTPOINT_WHITE"))
    )
    (comp (ref "TP5")
      (value "5012")
      (footprint "KSTN-5012_V")
      (description "Test Point, White, Through Hole, RoHS, Bulk")
      (fields (field (name "MANUFACTURER") "Keystone"))
      (libsource (lib "Altium Content Vault") (part "TESTPOINT_WHITE"))
    )
    (comp (ref "TP6")
      (value "5012")
      (footprint "KSTN-5012_V")
      (description "Test Point, White, Through Hole, RoHS, Bulk")
      (fields (field (name "MANUFACTURER") "Keystone"))
      (libsource (lib "Altium Content Vault") (part "TESTPOINT_WHITE"))
    )
    (comp (ref "TP7")
      (value "5012")
      (footprint "KSTN-5012_V")
      (description "Test Point, White, Through Hole, RoHS, Bulk")
      (fields (field (name "MANUFACTURER") "Keystone"))
      (libsource (lib "Altium Content Vault") (part "TESTPOINT_WHITE"))
    )
    (comp (ref "TP8")
      (value "5012")
      (footprint "KSTN-5012_V")
      (description "Test Point, White, Through Hole, RoHS, Bulk")
      (fields (field (name "MANUFACTURER") "Keystone"))
      (libsource (lib "Altium Content Vault") (part "TESTPOINT_WHITE"))
    )
    (comp (ref "TP9")
      (value "5012")
      (footprint "KSTN-5012_V")
      (description "Test Point, White, Through Hole, RoHS, Bulk")
      (fields (field (name "MANUFACTURER") "Keystone"))
      (libsource (lib "Altium Content Vault") (part "TESTPOINT_WHITE"))
    )
    (comp (ref "TP10")
      (value "5012")
      (footprint "KSTN-5012_V")
      (description "Test Point, White, Through Hole, RoHS, Bulk")
      (fields (field (name "MANUFACTURER") "Keystone"))
      (libsource (lib "Altium Content Vault") (part "TESTPOINT_WHITE"))
    )
    (comp (ref "TP11")
      (value "5012")
      (footprint "KSTN-5012_V")
      (description "Test Point, White, Through Hole, RoHS, Bulk")
      (fields (field (name "MANUFACTURER") "Keystone"))
      (libsource (lib "Altium Content Vault") (part "TESTPOINT_WHITE"))
    )
    (comp (ref "TP12")
      (value "5012")
      (footprint "KSTN-5012_V")
      (description "Test Point, White, Through Hole, RoHS, Bulk")
      (fields (field (name "MANUFACTURER") "Keystone"))
      (libsource (lib "Altium Content Vault") (part "TESTPOINT_WHITE"))
    )
    (comp (ref "TP13")
      (value "5012")
      (footprint "KSTN-5012_V")
      (description "Test Point, White, Through Hole, RoHS, Bulk")
      (fields (field (name "MANUFACTURER") "Keystone"))
      (libsource (lib "Altium Content Vault") (part "TESTPOINT_WHITE"))
    )
    (comp (ref "TP14")
      (value "5012")
      (footprint "KSTN-5012_V")
      (description "Test Point, White, Through Hole, RoHS, Bulk")
      (fields (field (name "MANUFACTURER") "Keystone"))
      (libsource (lib "Altium Content Vault") (part "TESTPOINT_WHITE"))
    )
    (comp (ref "TP15")
      (value "5012")
      (footprint "KSTN-5012_V")
      (description "Test Point, White, Through Hole, RoHS, Bulk")
      (fields (field (name "MANUFACTURER") "Keystone"))
      (libsource (lib "Altium Content Vault") (part "TESTPOINT_WHITE"))
    )
    (comp (ref "TP16")
      (value "5012")
      (footprint "KSTN-5012_V")
      (description "Test Point, White, Through Hole, RoHS, Bulk")
      (fields (field (name "MANUFACTURER") "Keystone"))
      (libsource (lib "Altium Content Vault") (part "TESTPOINT_WHITE"))
    )
    (comp (ref "TP17")
      (value "5012")
      (footprint "KSTN-5012_V")
      (description "Test Point, White, Through Hole, RoHS, Bulk")
      (fields (field (name "MANUFACTURER") "Keystone"))
      (libsource (lib "Altium Content Vault") (part "TESTPOINT_WHITE"))
    )
    (comp (ref "TP18")
      (value "5012")
      (footprint "KSTN-5012_V")
      (description "Test Point, White, Through Hole, RoHS, Bulk")
      (fields (field (name "MANUFACTURER") "Keystone"))
      (libsource (lib "Altium Content Vault") (part "TESTPOINT_WHITE"))
    )
    (comp (ref "TP19")
      (value "5012")
      (footprint "KSTN-5012_V")
      (description "Test Point, White, Through Hole, RoHS, Bulk")
      (fields (field (name "MANUFACTURER") "Keystone"))
      (libsource (lib "Altium Content Vault") (part "TESTPOINT_WHITE"))
    )
    (comp (ref "TP20")
      (value "5012")
      (footprint "KSTN-5012_V")
      (description "Test Point, White, Through Hole, RoHS, Bulk")
      (fields (field (name "MANUFACTURER") "Keystone"))
      (libsource (lib "Altium Content Vault") (part "TESTPOINT_WHITE"))
    )
    (comp (ref "TP21")
      (value "5012")
      (footprint "KSTN-5012_V")
      (description "Test Point, White, Through Hole, RoHS, Bulk")
      (fields (field (name "MANUFACTURER") "Keystone"))
      (libsource (lib "Altium Content Vault") (part "TESTPOINT_WHITE"))
    )
    (comp (ref "TP22")
      (value "5012")
      (footprint "KSTN-5012_V")
      (description "Test Point, White, Through Hole, RoHS, Bulk")
      (fields (field (name "MANUFACTURER") "Keystone"))
      (libsource (lib "Altium Content Vault") (part "TESTPOINT_WHITE"))
    )
    (comp (ref "TP23")
      (value "5012")
      (footprint "KSTN-5012_V")
      (description "Test Point, White, Through Hole, RoHS, Bulk")
      (fields (field (name "MANUFACTURER") "Keystone"))
      (libsource (lib "Altium Content Vault") (part "TESTPOINT_WHITE"))
    )
    (comp (ref "TP24")
      (value "5012")
      (footprint "KSTN-5012_V")
      (description "Test Point, White, Through Hole, RoHS, Bulk")
      (fields (field (name "MANUFACTURER") "Keystone"))
      (libsource (lib "Altium Content Vault") (part "TESTPOINT_WHITE"))
    )
    (comp (ref "TP25")
      (value "5012")
      (footprint "KSTN-5012_V")
      (description "Test Point, White, Through Hole, RoHS, Bulk")
      (fields (field (name "MANUFACTURER") "Keystone"))
      (libsource (lib "Altium Content Vault") (part "TESTPOINT_WHITE"))
    )
    (comp (ref "TP26")
      (value "5012")
      (footprint "KSTN-5012_V")
      (description "Test Point, White, Through Hole, RoHS, Bulk")
      (fields (field (name "MANUFACTURER") "Keystone"))
      (libsource (lib "Altium Content Vault") (part "TESTPOINT_WHITE"))
    )
    (comp (ref "TP27")
      (value "5012")
      (footprint "KSTN-5012_V")
      (description "Test Point, White, Through Hole, RoHS, Bulk")
      (fields (field (name "MANUFACTURER") "Keystone"))
      (libsource (lib "Altium Content Vault") (part "TESTPOINT_WHITE"))
    )
    (comp (ref "TP28")
      (value "5012")
      (footprint "KSTN-5012_V")
      (description "Test Point, White, Through Hole, RoHS, Bulk")
      (fields (field (name "MANUFACTURER") "Keystone"))
      (libsource (lib "Altium Content Vault") (part "TESTPOINT_WHITE"))
    )
    (comp (ref "TP29")
      (value "5012")
      (footprint "KSTN-5012_V")
      (description "Test Point, White, Through Hole, RoHS, Bulk")
      (fields (field (name "MANUFACTURER") "Keystone"))
      (libsource (lib "Altium Content Vault") (part "TESTPOINT_WHITE"))
    )
    (comp (ref "TP30")
      (value "5012")
      (footprint "KSTN-5012_V")
      (description "Test Point, White, Through Hole, RoHS, Bulk")
      (fields (field (name "MANUFACTURER") "Keystone"))
      (libsource (lib "Altium Content Vault") (part "TESTPOINT_WHITE"))
    )
    (comp (ref "TP31")
      (value "5012")
      (footprint "KSTN-5012_V")
      (description "Test Point, White, Through Hole, RoHS, Bulk")
      (fields (field (name "MANUFACTURER") "Keystone"))
      (libsource (lib "Altium Content Vault") (part "TESTPOINT_WHITE"))
    )
    (comp (ref "TP32")
      (value "5012")
      (footprint "KSTN-5012_V")
      (description "Test Point, White, Through Hole, RoHS, Bulk")
      (fields (field (name "MANUFACTURER") "Keystone"))
      (libsource (lib "Altium Content Vault") (part "TESTPOINT_WHITE"))
    )
    (comp (ref "U1")
      (value "UCC5310MCDR")
      (footprint "FP-D0008B-MFG")
      (description "DGTL ISO 3KV 1CH GATE DRVR 8SOIC")
      (libsource (lib "Altium Content Vault") (part "93895eecc217e3662da2195d510e3ba"))
    )
    (comp (ref "U2")
      (value "UCC5310MCDR")
      (footprint "FP-D0008B-MFG")
      (description "DGTL ISO 3KV 1CH GATE DRVR 8SOIC")
      (libsource (lib "Altium Content Vault") (part "93895eecc217e3662da2195d510e3ba"))
    )
    (comp (ref "U3")
      (value "UCC5310MCDR")
      (footprint "FP-D0008B-MFG")
      (description "DGTL ISO 3KV 1CH GATE DRVR 8SOIC")
      (libsource (lib "Altium Content Vault") (part "93895eecc217e3662da2195d510e3ba"))
    )
    (comp (ref "U4")
      (value "UCC5310MCDR")
      (footprint "FP-D0008B-MFG")
      (description "DGTL ISO 3KV 1CH GATE DRVR 8SOIC")
      (libsource (lib "Altium Content Vault") (part "93895eecc217e3662da2195d510e3ba"))
    )
    (comp (ref "U5")
      (value "UCC5310MCDR")
      (footprint "FP-D0008B-MFG")
      (description "DGTL ISO 3KV 1CH GATE DRVR 8SOIC")
      (libsource (lib "Altium Content Vault") (part "93895eecc217e3662da2195d510e3ba"))
    )
    (comp (ref "U6")
      (value "UCC5310MCDR")
      (footprint "FP-D0008B-MFG")
      (description "DGTL ISO 3KV 1CH GATE DRVR 8SOIC")
      (libsource (lib "Altium Content Vault") (part "93895eecc217e3662da2195d510e3ba"))
    )
    (comp (ref "U7")
      (value "SN74AHCT244QDWR")
      (footprint "DW0020A_M")
      (description "Automotive Catalog Octal Buffers/Drivers With 3-State Outputs, DW0020A, LARGE T&R")
      (fields
        (field (name "GENERIC PART NUMBER") "SN74AHCT244Q")
        (field (name "MANUFACTURER") "Texas Instruments")
      )
      (libsource (lib "Altium Content Vault") (part "TI-SN54_74-XX020A-20"))
    )
  )
  (nets
    (net (code "1") (name "+5") (class "Default")
      (node (ref "C1") (pin "1") (pinfunction "1_1") (pintype "passive"))
      (node (ref "EN1") (pin "1") (pinfunction "1_1") (pintype "passive"))
      (node (ref "EN2") (pin "1") (pinfunction "1_1") (pintype "passive"))
      (node (ref "EN3") (pin "1") (pinfunction "1_1") (pintype "passive"))
      (node (ref "EN4") (pin "1") (pinfunction "1_1") (pintype "passive"))
      (node (ref "EN5") (pin "1") (pinfunction "1_1") (pintype "passive"))
      (node (ref "EN6") (pin "1") (pinfunction "1_1") (pintype "passive"))
      (node (ref "J1") (pin "1") (pinfunction "1_1") (pintype "passive"))
      (node (ref "J2") (pin "1") (pinfunction "1_1") (pintype "passive"))
      (node (ref "R30") (pin "2") (pinfunction "2_2") (pintype "passive"))
      (node (ref "R32") (pin "2") (pinfunction "2_2") (pintype "passive"))
      (node (ref "R35") (pin "1") (pinfunction "1_1") (pintype "passive"))
      (node (ref "U7") (pin "20") (pinfunction "VCC_20") (pintype "power_in"))
    )
    (net (code "2") (name "/Buffer1") (class "Default")
      (node (ref "R19") (pin "1") (pinfunction "1_1") (pintype "passive"))
      (node (ref "R21") (pin "2") (pinfunction "2_2") (pintype "passive"))
      (node (ref "TP3") (pin "1") (pinfunction "1_1") (pintype "passive"))
      (node (ref "U1") (pin "2") (pinfunction "IN+_2") (pintype "input"))
      (node (ref "U7") (pin "18") (pinfunction "1Y1_18") (pintype "tri_state"))
    )
    (net (code "3") (name "/Buffer2") (class "Default")
      (node (ref "R20") (pin "1") (pinfunction "1_1") (pintype "passive"))
      (node (ref "R23") (pin "2") (pinfunction "2_2") (pintype "passive"))
      (node (ref "TP4") (pin "1") (pinfunction "1_1") (pintype "passive"))
      (node (ref "U2") (pin "2") (pinfunction "IN+_2") (pintype "input"))
      (node (ref "U7") (pin "16") (pinfunction "1Y2_16") (pintype "tri_state"))
    )
    (net (code "4") (name "/Buffer3") (class "Default")
      (node (ref "R22") (pin "1") (pinfunction "1_1") (pintype "passive"))
      (node (ref "R25") (pin "2") (pinfunction "2_2") (pintype "passive"))
      (node (ref "TP5") (pin "1") (pinfunction "1_1") (pintype "passive"))
      (node (ref "U3") (pin "2") (pinfunction "IN+_2") (pintype "input"))
      (node (ref "U7") (pin "14") (pinfunction "1Y3_14") (pintype "tri_state"))
    )
    (net (code "5") (name "/Buffer4") (class "Default")
      (node (ref "R24") (pin "1") (pinfunction "1_1") (pintype "passive"))
      (node (ref "R27") (pin "2") (pinfunction "2_2") (pintype "passive"))
      (node (ref "TP6") (pin "1") (pinfunction "1_1") (pintype "passive"))
      (node (ref "U4") (pin "2") (pinfunction "IN+_2") (pintype "input"))
      (node (ref "U7") (pin "12") (pinfunction "1Y4_12") (pintype "tri_state"))
    )
    (net (code "6") (name "/Buffer5") (class "Default")
      (node (ref "R26") (pin "1") (pinfunction "1_1") (pintype "passive"))
      (node (ref "R29") (pin "2") (pinfunction "2_2") (pintype "passive"))
      (node (ref "TP7") (pin "1") (pinfunction "1_1") (pintype "passive"))
      (node (ref "U5") (pin "2") (pinfunction "IN+_2") (pintype "input"))
      (node (ref "U7") (pin "9") (pinfunction "2Y1_9") (pintype "tri_state"))
    )
    (net (code "7") (name "/Buffer6") (class "Default")
      (node (ref "R28") (pin "1") (pinfunction "1_1") (pintype "passive"))
      (node (ref "R31") (pin "2") (pinfunction "2_2") (pintype "passive"))
      (node (ref "TP8") (pin "1") (pinfunction "1_1") (pintype "passive"))
      (node (ref "U6") (pin "2") (pinfunction "IN+_2") (pintype "input"))
      (node (ref "U7") (pin "7") (pinfunction "2Y2_7") (pintype "tri_state"))
    )
    (net (code "8") (name "/Enable1") (class "Default")
      (node (ref "J3") (pin "1") (pinfunction "1_1") (pintype "passive"))
      (node (ref "R30") (pin "1") (pinfunction "1_1") (pintype "passive"))
      (node (ref "R33") (pin "1") (pinfunction "1_1") (pintype "passive"))
      (node (ref "U7") (pin "1") (pinfunction "1~{OE}_1") (pintype "input"))
    )
    (net (code "9") (name "/Enable2") (class "Default")
      (node (ref "J3") (pin "2") (pinfunction "2_2") (pintype "passive"))
      (node (ref "R32") (pin "1") (pinfunction "1_1") (pintype "passive"))
      (node (ref "R34") (pin "1") (pinfunction "1_1") (pintype "passive"))
      (node (ref "U7") (pin "19") (pinfunction "2~{OE}_19") (pintype "input"))
    )
    (net (code "10") (name "/Gate1") (class "Default")
      (node (ref "J8") (pin "1") (pinfunction "1_1") (pintype "passive"))
      (node (ref "R2") (pin "2") (pinfunction "2_2") (pintype "passive"))
      (node (ref "TP10") (pin "1") (pinfunction "1_1") (pintype "passive"))
      (node (ref "U1") (pin "7") (pinfunction "CLAMP_7") (pintype "passive"))
    )
    (net (code "11") (name "/Gate2") (class "Default")
      (node (ref "J9") (pin "1") (pinfunction "1_1") (pintype "passive"))
      (node (ref "R4") (pin "2") (pinfunction "2_2") (pintype "passive"))
      (node (ref "TP13") (pin "1") (pinfunction "1_1") (pintype "passive"))
      (node (ref "U2") (pin "7") (pinfunction "CLAMP_7") (pintype "passive"))
    )
    (net (code "12") (name "/Gate3") (class "Default")
      (node (ref "J11") (pin "1") (pinfunction "1_1") (pintype "passive"))
      (node (ref "R6") (pin "2") (pinfunction "2_2") (pintype "passive"))
      (node (ref "TP16") (pin "1") (pinfunction "1_1") (pintype "passive"))
      (node (ref "U3") (pin "7") (pinfunction "CLAMP_7") (pintype "passive"))
    )
    (net (code "13") (name "/Gate4") (class "Default")
      (node (ref "J12") (pin "1") (pinfunction "1_1") (pintype "passive"))
      (node (ref "R8") (pin "2") (pinfunction "2_2") (pintype "passive"))
      (node (ref "TP21") (pin "1") (pinfunction "1_1") (pintype "passive"))
      (node (ref "U4") (pin "7") (pinfunction "CLAMP_7") (pintype "passive"))
    )
    (net (code "14") (name "/Gate5") (class "Default")
      (node (ref "J13") (pin "1") (pinfunction "1_1") (pintype "passive"))
      (node (ref "R10") (pin "2") (pinfunction "2_2") (pintype "passive"))
      (node (ref "TP27") (pin "1") (pinfunction "1_1") (pintype "passive"))
      (node (ref "U5") (pin "7") (pinfunction "CLAMP_7") (pintype "passive"))
    )
    (net (code "15") (name "/Gate6") (class "Default")
      (node (ref "J14") (pin "1") (pinfunction "1_1") (pintype "passive"))
      (node (ref "R12") (pin "2") (pinfunction "2_2") (pintype "passive"))
      (node (ref "TP31") (pin "1") (pinfunction "1_1") (pintype "passive"))
      (node (ref "U6") (pin "7") (pinfunction "CLAMP_7") (pintype "passive"))
    )
    (net (code "16") (name "/ISOL1+") (class "Default")
      (node (ref "C13") (pin "1") (pinfunction "1_1") (pintype "passive"))
      (node (ref "C15") (pin "1") (pinfunction "1_1") (pintype "passive"))
      (node (ref "C17") (pin "1") (pinfunction "1_1") (pintype "passive"))
      (node (ref "C18") (pin "1") (pinfunction "1_1") (pintype "passive"))
      (node (ref "D1") (pin "1") (pinfunction "K_1") (pintype "passive"))
      (node (ref "PS1") (pin "6") (pinfunction "+VOUT_6") (pintype "power_in"))
      (node (ref "R1") (pin "1") (pinfunction "1_1") (pintype "passive"))
      (node (ref "R37") (pin "1") (pinfunction "1_1") (pintype "passive"))
      (node (ref "TP9") (pin "1") (pinfunction "1_1") (pintype "passive"))
      (node (ref "U1") (pin "5") (pinfunction "VCC2_5") (pintype "power_in"))
    )
    (net (code "17") (name "/ISOL1-") (class "Default")
      (node (ref "C13") (pin "2") (pinfunction "2_2") (pintype "passive"))
      (node (ref "C15") (pin "2") (pinfunction "2_2") (pintype "passive"))
      (node (ref "C17") (pin "2") (pinfunction "2_2") (pintype "passive"))
      (node (ref "C18") (pin "2") (pinfunction "2_2") (pintype "passive"))
      (node (ref "D1") (pin "2") (pinfunction "A_2") (pintype "passive"))
      (node (ref "DS2") (pin "1") (pinfunction "K_1") (pintype "passive"))
      (node (ref "J8") (pin "2") (pinfunction "2_2") (pintype "passive"))
      (node (ref "PS1") (pin "4") (pinfunction "-VOUT_4") (pintype "power_in"))
      (node (ref "R1") (pin "2") (pinfunction "2_2") (pintype "passive"))
      (node (ref "TP11") (pin "1") (pinfunction "1_1") (pintype "passive"))
      (node (ref "U1") (pin "8") (pinfunction "VEE2_8") (pintype "power_in"))
    )
    (net (code "18") (name "/ISOL2+") (class "Default")
      (node (ref "C19") (pin "1") (pinfunction "1_1") (pintype "passive"))
      (node (ref "C21") (pin "1") (pinfunction "1_1") (pintype "passive"))
      (node (ref "C23") (pin "1") (pinfunction "1_1") (pintype "passive"))
      (node (ref "C24") (pin "1") (pinfunction "1_1") (pintype "passive"))
      (node (ref "D2") (pin "1") (pinfunction "K_1") (pintype "passive"))
      (node (ref "PS2") (pin "6") (pinfunction "+VOUT_6") (pintype "power_in"))
      (node (ref "R3") (pin "1") (pinfunction "1_1") (pintype "passive"))
      (node (ref "R38") (pin "1") (pinfunction "1_1") (pintype "passive"))
      (node (ref "TP12") (pin "1") (pinfunction "1_1") (pintype "passive"))
      (node (ref "U2") (pin "5") (pinfunction "VCC2_5") (pintype "power_in"))
    )
    (net (code "19") (name "/ISOL2-") (class "Default")
      (node (ref "C19") (pin "2") (pinfunction "2_2") (pintype "passive"))
      (node (ref "C21") (pin "2") (pinfunction "2_2") (pintype "passive"))
      (node (ref "C23") (pin "2") (pinfunction "2_2") (pintype "passive"))
      (node (ref "C24") (pin "2") (pinfunction "2_2") (pintype "passive"))
      (node (ref "D2") (pin "2") (pinfunction "A_2") (pintype "passive"))
      (node (ref "DS3") (pin "1") (pinfunction "K_1") (pintype "passive"))
      (node (ref "J9") (pin "2") (pinfunction "2_2") (pintype "passive"))
      (node (ref "PS2") (pin "4") (pinfunction "-VOUT_4") (pintype "power_in"))
      (node (ref "R3") (pin "2") (pinfunction "2_2") (pintype "passive"))
      (node (ref "TP14") (pin "1") (pinfunction "1_1") (pintype "passive"))
      (node (ref "U2") (pin "8") (pinfunction "VEE2_8") (pintype "power_in"))
    )
    (net (code "20") (name "/ISOL3+") (class "Default")
      (node (ref "C25") (pin "1") (pinfunction "1_1") (pintype "passive"))
      (node (ref "C27") (pin "1") (pinfunction "1_1") (pintype "passive"))
      (node (ref "C29") (pin "1") (pinfunction "1_1") (pintype "passive"))
      (node (ref "C30") (pin "1") (pinfunction "1_1") (pintype "passive"))
      (node (ref "D3") (pin "1") (pinfunction "K_1") (pintype "passive"))
      (node (ref "PS3") (pin "6") (pinfunction "+VOUT_6") (pintype "power_in"))
      (node (ref "R39") (pin "1") (pinfunction "1_1") (pintype "passive"))
      (node (ref "R5") (pin "1") (pinfunction "1_1") (pintype "passive"))
      (node (ref "TP15") (pin "1") (pinfunction "1_1") (pintype "passive"))
      (node (ref "U3") (pin "5") (pinfunction "VCC2_5") (pintype "power_in"))
    )
    (net (code "21") (name "/ISOL3-") (class "Default")
      (node (ref "C25") (pin "2") (pinfunction "2_2") (pintype "passive"))
      (node (ref "C27") (pin "2") (pinfunction "2_2") (pintype "passive"))
      (node (ref "C29") (pin "2") (pinfunction "2_2") (pintype "passive"))
      (node (ref "C30") (pin "2") (pinfunction "2_2") (pintype "passive"))
      (node (ref "D3") (pin "2") (pinfunction "A_2") (pintype "passive"))
      (node (ref "DS5") (pin "1") (pinfunction "K_1") (pintype "passive"))
      (node (ref "J11") (pin "2") (pinfunction "2_2") (pintype "passive"))
      (node (ref "PS3") (pin "4") (pinfunction "-VOUT_4") (pintype "power_in"))
      (node (ref "R5") (pin "2") (pinfunction "2_2") (pintype "passive"))
      (node (ref "TP17") (pin "1") (pinfunction "1_1") (pintype "passive"))
      (node (ref "U3") (pin "8") (pinfunction "VEE2_8") (pintype "power_in"))
    )
    (net (code "22") (name "/ISOL4+") (class "Default")
      (node (ref "C31") (pin "1") (pinfunction "1_1") (pintype "passive"))
      (node (ref "C33") (pin "1") (pinfunction "1_1") (pintype "passive"))
      (node (ref "C35") (pin "1") (pinfunction "1_1") (pintype "passive"))
      (node (ref "C36") (pin "1") (pinfunction "1_1") (pintype "passive"))
      (node (ref "D4") (pin "1") (pinfunction "K_1") (pintype "passive"))
      (node (ref "PS4") (pin "6") (pinfunction "+VOUT_6") (pintype "power_in"))
      (node (ref "R40") (pin "1") (pinfunction "1_1") (pintype "passive"))
      (node (ref "R7") (pin "1") (pinfunction "1_1") (pintype "passive"))
      (node (ref "TP19") (pin "1") (pinfunction "1_1") (pintype "passive"))
      (node (ref "U4") (pin "5") (pinfunction "VCC2_5") (pintype "power_in"))
    )
    (net (code "23") (name "/ISOL4-") (class "Default")
      (node (ref "C31") (pin "2") (pinfunction "2_2") (pintype "passive"))
      (node (ref "C33") (pin "2") (pinfunction "2_2") (pintype "passive"))
      (node (ref "C35") (pin "2") (pinfunction "2_2") (pintype "passive"))
      (node (ref "C36") (pin "2") (pinfunction "2_2") (pintype "passive"))
      (node (ref "D4") (pin "2") (pinfunction "A_2") (pintype "passive"))
      (node (ref "DS7") (pin "1") (pinfunction "K_1") (pintype "passive"))
      (node (ref "J12") (pin "2") (pinfunction "2_2") (pintype "passive"))
      (node (ref "PS4") (pin "4") (pinfunction "-VOUT_4") (pintype "power_in"))
      (node (ref "R7") (pin "2") (pinfunction "2_2") (pintype "passive"))
      (node (ref "TP22") (pin "1") (pinfunction "1_1") (pintype "passive"))
      (node (ref "U4") (pin "8") (pinfunction "VEE2_8") (pintype "power_in"))
    )
    (net (code "24") (name "/ISOL5+") (class "Default")
      (node (ref "C37") (pin "1") (pinfunction "1_1") (pintype "passive"))
      (node (ref "C39") (pin "1") (pinfunction "1_1") (pintype "passive"))
      (node (ref "C41") (pin "1") (pinfunction "1_1") (pintype "passive"))
      (node (ref "C42") (pin "1") (pinfunction "1_1") (pintype "passive"))
      (node (ref "D5") (pin "1") (pinfunction "K_1") (pintype "passive"))
      (node (ref "PS5") (pin "6") (pinfunction "+VOUT_6") (pintype "power_in"))
      (node (ref "R41") (pin "1") (pinfunction "1_1") (pintype "passive"))
      (node (ref "R9") (pin "1") (pinfunction "1_1") (pintype "passive"))
      (node (ref "TP25") (pin "1") (pinfunction "1_1") (pintype "passive"))
      (node (ref "U5") (pin "5") (pinfunction "VCC2_5") (pintype "power_in"))
    )
    (net (code "25") (name "/ISOL5-") (class "Default")
      (node (ref "C37") (pin "2") (pinfunction "2_2") (pintype "passive"))
      (node (ref "C39") (pin "2") (pinfunction "2_2") (pintype "passive"))
      (node (ref "C41") (pin "2") (pinfunction "2_2") (pintype "passive"))
      (node (ref "C42") (pin "2") (pinfunction "2_2") (pintype "passive"))
      (node (ref "D5") (pin "2") (pinfunction "A_2") (pintype "passive"))
      (node (ref "DS8") (pin "1") (pinfunction "K_1") (pintype "passive"))
      (node (ref "J13") (pin "2") (pinfunction "2_2") (pintype "passive"))
      (node (ref "PS5") (pin "4") (pinfunction "-VOUT_4") (pintype "power_in"))
      (node (ref "R9") (pin "2") (pinfunction "2_2") (pintype "passive"))
      (node (ref "TP28") (pin "1") (pinfunction "1_1") (pintype "passive"))
      (node (ref "U5") (pin "8") (pinfunction "VEE2_8") (pintype "power_in"))
    )
    (net (code "26") (name "/ISOL6+") (class "Default")
      (node (ref "C43") (pin "1") (pinfunction "1_1") (pintype "passive"))
      (node (ref "C45") (pin "1") (pinfunction "1_1") (pintype "passive"))
      (node (ref "C47") (pin "1") (pinfunction "1_1") (pintype "passive"))
      (node (ref "C48") (pin "1") (pinfunction "1_1") (pintype "passive"))
      (node (ref "D6") (pin "1") (pinfunction "K_1") (pintype "passive"))
      (node (ref "PS6") (pin "6") (pinfunction "+VOUT_6") (pintype "power_in"))
      (node (ref "R11") (pin "1") (pinfunction "1_1") (pintype "passive"))
      (node (ref "R42") (pin "1") (pinfunction "1_1") (pintype "passive"))
      (node (ref "TP30") (pin "1") (pinfunction "1_1") (pintype "passive"))
      (node (ref "U6") (pin "5") (pinfunction "VCC2_5") (pintype "power_in"))
    )
    (net (code "27") (name "/ISOL6-") (class "Default")
      (node (ref "C43") (pin "2") (pinfunction "2_2") (pintype "passive"))
      (node (ref "C45") (pin "2") (pinfunction "2_2") (pintype "passive"))
      (node (ref "C47") (pin "2") (pinfunction "2_2") (pintype "passive"))
      (node (ref "C48") (pin "2") (pinfunction "2_2") (pintype "passive"))
      (node (ref "D6") (pin "2") (pinfunction "A_2") (pintype "passive"))
      (node (ref "DS9") (pin "1") (pinfunction "K_1") (pintype "passive"))
      (node (ref "J14") (pin "2") (pinfunction "2_2") (pintype "passive"))
      (node (ref "PS6") (pin "4") (pinfunction "-VOUT_4") (pintype "power_in"))
      (node (ref "R11") (pin "2") (pinfunction "2_2") (pintype "passive"))
      (node (ref "TP32") (pin "1") (pinfunction "1_1") (pintype "passive"))
      (node (ref "U6") (pin "8") (pinfunction "VEE2_8") (pintype "power_in"))
    )
    (net (code "28") (name "/PWM1") (class "Default")
      (node (ref "J10") (pin "1") (pinfunction "1_1") (pintype "passive"))
      (node (ref "R13") (pin "1") (pinfunction "1_1") (pintype "passive"))
      (node (ref "TP18") (pin "1") (pinfunction "1_1") (pintype "passive"))
      (node (ref "U7") (pin "2") (pinfunction "1A1_2") (pintype "input"))
    )
    (net (code "29") (name "/PWM2") (class "Default")
      (node (ref "J10") (pin "2") (pinfunction "2_2") (pintype "passive"))
      (node (ref "R14") (pin "1") (pinfunction "1_1") (pintype "passive"))
      (node (ref "TP20") (pin "1") (pinfunction "1_1") (pintype "passive"))
      (node (ref "U7") (pin "4") (pinfunction "1A2_4") (pintype "input"))
    )
    (net (code "30") (name "/PWM3") (class "Default")
      (node (ref "J10") (pin "3") (pinfunction "3_3") (pintype "passive"))
      (node (ref "R15") (pin "1") (pinfunction "1_1") (pintype "passive"))
      (node (ref "TP23") (pin "1") (pinfunction "1_1") (pintype "passive"))
      (node (ref "U7") (pin "6") (pinfunction "1A3_6") (pintype "input"))
    )
    (net (code "31") (name "/PWM4") (class "Default")
      (node (ref "J10") (pin "4") (pinfunction "4_4") (pintype "passive"))
      (node (ref "R16") (pin "1") (pinfunction "1_1") (pintype "passive"))
      (node (ref "TP24") (pin "1") (pinfunction "1_1") (pintype "passive"))
      (node (ref "U7") (pin "8") (pinfunction "1A4_8") (pintype "input"))
    )
    (net (code "32") (name "/PWM5") (class "Default")
      (node (ref "J10") (pin "5") (pinfunction "5_5") (pintype "passive"))
      (node (ref "R17") (pin "1") (pinfunction "1_1") (pintype "passive"))
      (node (ref "TP26") (pin "1") (pinfunction "1_1") (pintype "passive"))
      (node (ref "U7") (pin "11") (pinfunction "2A1_11") (pintype "input"))
    )
    (net (code "33") (name "/PWM6") (class "Default")
      (node (ref "J10") (pin "6") (pinfunction "6_6") (pintype "passive"))
      (node (ref "R18") (pin "1") (pinfunction "1_1") (pintype "passive"))
      (node (ref "TP29") (pin "1") (pinfunction "1_1") (pintype "passive"))
      (node (ref "U7") (pin "13") (pinfunction "2A2_13") (pintype "input"))
    )
    (net (code "34") (name "GND") (class "Default")
      (node (ref "C1") (pin "2") (pinfunction "2_2") (pintype "passive"))
      (node (ref "C14") (pin "2") (pinfunction "2_2") (pintype "passive"))
      (node (ref "C16") (pin "2") (pinfunction "2_2") (pintype "passive"))
      (node (ref "C20") (pin "2") (pinfunction "2_2") (pintype "passive"))
      (node (ref "C22") (pin "2") (pinfunction "2_2") (pintype "passive"))
      (node (ref "C26") (pin "2") (pinfunction "2_2") (pintype "passive"))
      (node (ref "C28") (pin "2") (pinfunction "2_2") (pintype "passive"))
      (node (ref "C32") (pin "2") (pinfunction "2_2") (pintype "passive"))
      (node (ref "C34") (pin "2") (pinfunction "2_2") (pintype "passive"))
      (node (ref "C38") (pin "2") (pinfunction "2_2") (pintype "passive"))
      (node (ref "C40") (pin "2") (pinfunction "2_2") (pintype "passive"))
      (node (ref "C44") (pin "2") (pinfunction "2_2") (pintype "passive"))
      (node (ref "C46") (pin "2") (pinfunction "2_2") (pintype "passive"))
      (node (ref "DS1") (pin "1") (pinfunction "K_1") (pintype "passive"))
      (node (ref "DS4") (pin "1") (pinfunction "K_1") (pintype "passive"))
      (node (ref "DS6") (pin "1") (pinfunction "K_1") (pintype "passive"))
      (node (ref "J1") (pin "2") (pinfunction "2_2") (pintype "passive"))
      (node (ref "J2") (pin "2") (pinfunction "2_2") (pintype "passive"))
      (node (ref "PS1") (pin "2") (pinfunction "-VIN_2") (pintype "power_in"))
      (node (ref "PS2") (pin "2") (pinfunction "-VIN_2") (pintype "power_in"))
      (node (ref "PS3") (pin "2") (pinfunction "-VIN_2") (pintype "power_in"))
      (node (ref "PS4") (pin "2") (pinfunction "-VIN_2") (pintype "power_in"))
      (node (ref "PS5") (pin "2") (pinfunction "-VIN_2") (pintype "power_in"))
      (node (ref "PS6") (pin "2") (pinfunction "-VIN_2") (pintype "power_in"))
      (node (ref "R13") (pin "2") (pinfunction "2_2") (pintype "passive"))
      (node (ref "R14") (pin "2") (pinfunction "2_2") (pintype "passive"))
      (node (ref "R15") (pin "2") (pinfunction "2_2") (pintype "passive"))
      (node (ref "R16") (pin "2") (pinfunction "2_2") (pintype "passive"))
      (node (ref "R17") (pin "2") (pinfunction "2_2") (pintype "passive"))
      (node (ref "R18") (pin "2") (pinfunction "2_2") (pintype "passive"))
      (node (ref "R19") (pin "2") (pinfunction "2_2") (pintype "passive"))
      (node (ref "R20") (pin "2") (pinfunction "2_2") (pintype "passive"))
      (node (ref "R21") (pin "1") (pinfunction "1_1") (pintype "passive"))
      (node (ref "R22") (pin "2") (pinfunction "2_2") (pintype "passive"))
      (node (ref "R23") (pin "1") (pinfunction "1_1") (pintype "passive"))
      (node (ref "R24") (pin "2") (pinfunction "2_2") (pintype "passive"))
      (node (ref "R25") (pin "1") (pinfunction "1_1") (pintype "passive"))
      (node (ref "R26") (pin "2") (pinfunction "2_2") (pintype "passive"))
      (node (ref "R27") (pin "1") (pinfunction "1_1") (pintype "passive"))
      (node (ref "R28") (pin "2") (pinfunction "2_2") (pintype "passive"))
      (node (ref "R29") (pin "1") (pinfunction "1_1") (pintype "passive"))
      (node (ref "R31") (pin "1") (pinfunction "1_1") (pintype "passive"))
      (node (ref "U1") (pin "3") (pinfunction "IN-_3") (pintype "input"))
      (node (ref "U1") (pin "4") (pinfunction "GND1_4") (pintype "power_in"))
      (node (ref "U2") (pin "3") (pinfunction "IN-_3") (pintype "input"))
      (node (ref "U2") (pin "4") (pinfunction "GND1_4") (pintype "power_in"))
      (node (ref "U3") (pin "3") (pinfunction "IN-_3") (pintype "input"))
      (node (ref "U3") (pin "4") (pinfunction "GND1_4") (pintype "power_in"))
      (node (ref "U4") (pin "3") (pinfunction "IN-_3") (pintype "input"))
      (node (ref "U4") (pin "4") (pinfunction "GND1_4") (pintype "power_in"))
      (node (ref "U5") (pin "3") (pinfunction "IN-_3") (pintype "input"))
      (node (ref "U5") (pin "4") (pinfunction "GND1_4") (pintype "power_in"))
      (node (ref "U6") (pin "3") (pinfunction "IN-_3") (pintype "input"))
      (node (ref "U6") (pin "4") (pinfunction "GND1_4") (pintype "power_in"))
      (node (ref "U7") (pin "10") (pinfunction "GND_10") (pintype "power_in"))
      (node (ref "U7") (pin "15") (pinfunction "2A3_15") (pintype "input"))
      (node (ref "U7") (pin "17") (pinfunction "2A4_17") (pintype "input"))
    )
    (net (code "35") (name "Net-(DS1-A)") (class "Default")
      (node (ref "DS1") (pin "2") (pinfunction "A_2") (pintype "passive"))
      (node (ref "R35") (pin "2") (pinfunction "2_2") (pintype "passive"))
    )
    (net (code "36") (name "Net-(DS2-A)") (class "Default")
      (node (ref "DS2") (pin "2") (pinfunction "A_2") (pintype "passive"))
      (node (ref "R37") (pin "2") (pinfunction "2_2") (pintype "passive"))
    )
    (net (code "37") (name "Net-(DS3-A)") (class "Default")
      (node (ref "DS3") (pin "2") (pinfunction "A_2") (pintype "passive"))
      (node (ref "R38") (pin "2") (pinfunction "2_2") (pintype "passive"))
    )
    (net (code "38") (name "Net-(DS4-A)") (class "Default")
      (node (ref "DS4") (pin "2") (pinfunction "A_2") (pintype "passive"))
      (node (ref "R34") (pin "2") (pinfunction "2_2") (pintype "passive"))
    )
    (net (code "39") (name "Net-(DS5-A)") (class "Default")
      (node (ref "DS5") (pin "2") (pinfunction "A_2") (pintype "passive"))
      (node (ref "R39") (pin "2") (pinfunction "2_2") (pintype "passive"))
    )
    (net (code "40") (name "Net-(DS6-A)") (class "Default")
      (node (ref "DS6") (pin "2") (pinfunction "A_2") (pintype "passive"))
      (node (ref "R33") (pin "2") (pinfunction "2_2") (pintype "passive"))
    )
    (net (code "41") (name "Net-(DS7-A)") (class "Default")
      (node (ref "DS7") (pin "2") (pinfunction "A_2") (pintype "passive"))
      (node (ref "R40") (pin "2") (pinfunction "2_2") (pintype "passive"))
    )
    (net (code "42") (name "Net-(DS8-A)") (class "Default")
      (node (ref "DS8") (pin "2") (pinfunction "A_2") (pintype "passive"))
      (node (ref "R41") (pin "2") (pinfunction "2_2") (pintype "passive"))
    )
    (net (code "43") (name "Net-(DS9-A)") (class "Default")
      (node (ref "DS9") (pin "2") (pinfunction "A_2") (pintype "passive"))
      (node (ref "R42") (pin "2") (pinfunction "2_2") (pintype "passive"))
    )
    (net (code "44") (name "Net-(PS1-+VIN)") (class "Default")
      (node (ref "C14") (pin "1") (pinfunction "1_1") (pintype "passive"))
      (node (ref "C16") (pin "1") (pinfunction "1_1") (pintype "passive"))
      (node (ref "EN1") (pin "2") (pinfunction "2_2") (pintype "passive"))
      (node (ref "PS1") (pin "1") (pinfunction "+VIN_1") (pintype "power_in"))
      (node (ref "U1") (pin "1") (pinfunction "VCC1_1") (pintype "power_in"))
    )
    (net (code "45") (name "Net-(PS2-+VIN)") (class "Default")
      (node (ref "C20") (pin "1") (pinfunction "1_1") (pintype "passive"))
      (node (ref "C22") (pin "1") (pinfunction "1_1") (pintype "passive"))
      (node (ref "EN2") (pin "2") (pinfunction "2_2") (pintype "passive"))
      (node (ref "PS2") (pin "1") (pinfunction "+VIN_1") (pintype "power_in"))
      (node (ref "U2") (pin "1") (pinfunction "VCC1_1") (pintype "power_in"))
    )
    (net (code "46") (name "Net-(PS3-+VIN)") (class "Default")
      (node (ref "C26") (pin "1") (pinfunction "1_1") (pintype "passive"))
      (node (ref "C28") (pin "1") (pinfunction "1_1") (pintype "passive"))
      (node (ref "EN3") (pin "2") (pinfunction "2_2") (pintype "passive"))
      (node (ref "PS3") (pin "1") (pinfunction "+VIN_1") (pintype "power_in"))
      (node (ref "U3") (pin "1") (pinfunction "VCC1_1") (pintype "power_in"))
    )
    (net (code "47") (name "Net-(PS4-+VIN)") (class "Default")
      (node (ref "C32") (pin "1") (pinfunction "1_1") (pintype "passive"))
      (node (ref "C34") (pin "1") (pinfunction "1_1") (pintype "passive"))
      (node (ref "EN4") (pin "2") (pinfunction "2_2") (pintype "passive"))
      (node (ref "PS4") (pin "1") (pinfunction "+VIN_1") (pintype "power_in"))
      (node (ref "U4") (pin "1") (pinfunction "VCC1_1") (pintype "power_in"))
    )
    (net (code "48") (name "Net-(PS5-+VIN)") (class "Default")
      (node (ref "C38") (pin "1") (pinfunction "1_1") (pintype "passive"))
      (node (ref "C40") (pin "1") (pinfunction "1_1") (pintype "passive"))
      (node (ref "EN5") (pin "2") (pinfunction "2_2") (pintype "passive"))
      (node (ref "PS5") (pin "1") (pinfunction "+VIN_1") (pintype "power_in"))
      (node (ref "U5") (pin "1") (pinfunction "VCC1_1") (pintype "power_in"))
    )
    (net (code "49") (name "Net-(PS6-+VIN)") (class "Default")
      (node (ref "C44") (pin "1") (pinfunction "1_1") (pintype "passive"))
      (node (ref "C46") (pin "1") (pinfunction "1_1") (pintype "passive"))
      (node (ref "EN6") (pin "2") (pinfunction "2_2") (pintype "passive"))
      (node (ref "PS6") (pin "1") (pinfunction "+VIN_1") (pintype "power_in"))
      (node (ref "U6") (pin "1") (pinfunction "VCC1_1") (pintype "power_in"))
    )
    (net (code "50") (name "Net-(U1-OUT)") (class "Default")
      (node (ref "R2") (pin "1") (pinfunction "1_1") (pintype "passive"))
      (node (ref "U1") (pin "6") (pinfunction "OUT_6") (pintype "output"))
    )
    (net (code "51") (name "Net-(U2-OUT)") (class "Default")
      (node (ref "R4") (pin "1") (pinfunction "1_1") (pintype "passive"))
      (node (ref "U2") (pin "6") (pinfunction "OUT_6") (pintype "output"))
    )
    (net (code "52") (name "Net-(U3-OUT)") (class "Default")
      (node (ref "R6") (pin "1") (pinfunction "1_1") (pintype "passive"))
      (node (ref "U3") (pin "6") (pinfunction "OUT_6") (pintype "output"))
    )
    (net (code "53") (name "Net-(U4-OUT)") (class "Default")
      (node (ref "R8") (pin "1") (pinfunction "1_1") (pintype "passive"))
      (node (ref "U4") (pin "6") (pinfunction "OUT_6") (pintype "output"))
    )
    (net (code "54") (name "Net-(U5-OUT)") (class "Default")
      (node (ref "R10") (pin "1") (pinfunction "1_1") (pintype "passive"))
      (node (ref "U5") (pin "6") (pinfunction "OUT_6") (pintype "output"))
    )
    (net (code "55") (name "Net-(U6-OUT)") (class "Default")
      (node (ref "R12") (pin "1") (pinfunction "1_1") (pintype "passive"))
      (node (ref "U6") (pin "6") (pinfunction "OUT_6") (pintype "output"))
    )
    (net (code "56") (name "unconnected-(U7B-2Y3-Pad5)") (class "Default")
      (node (ref "U7") (pin "5") (pinfunction "2Y3_5") (pintype "tri_state+no_connect"))
    )
    (net (code "57") (name "unconnected-(U7B-2Y4-Pad3)") (class "Default")
      (node (ref "U7") (pin "3") (pinfunction "2Y4_3") (pintype "tri_state+no_connect"))
    )
  )
)
